# Parallel_CS_Prototype_multiple_sources.net
KiCad netlist of a schematic drawn in EAGLE
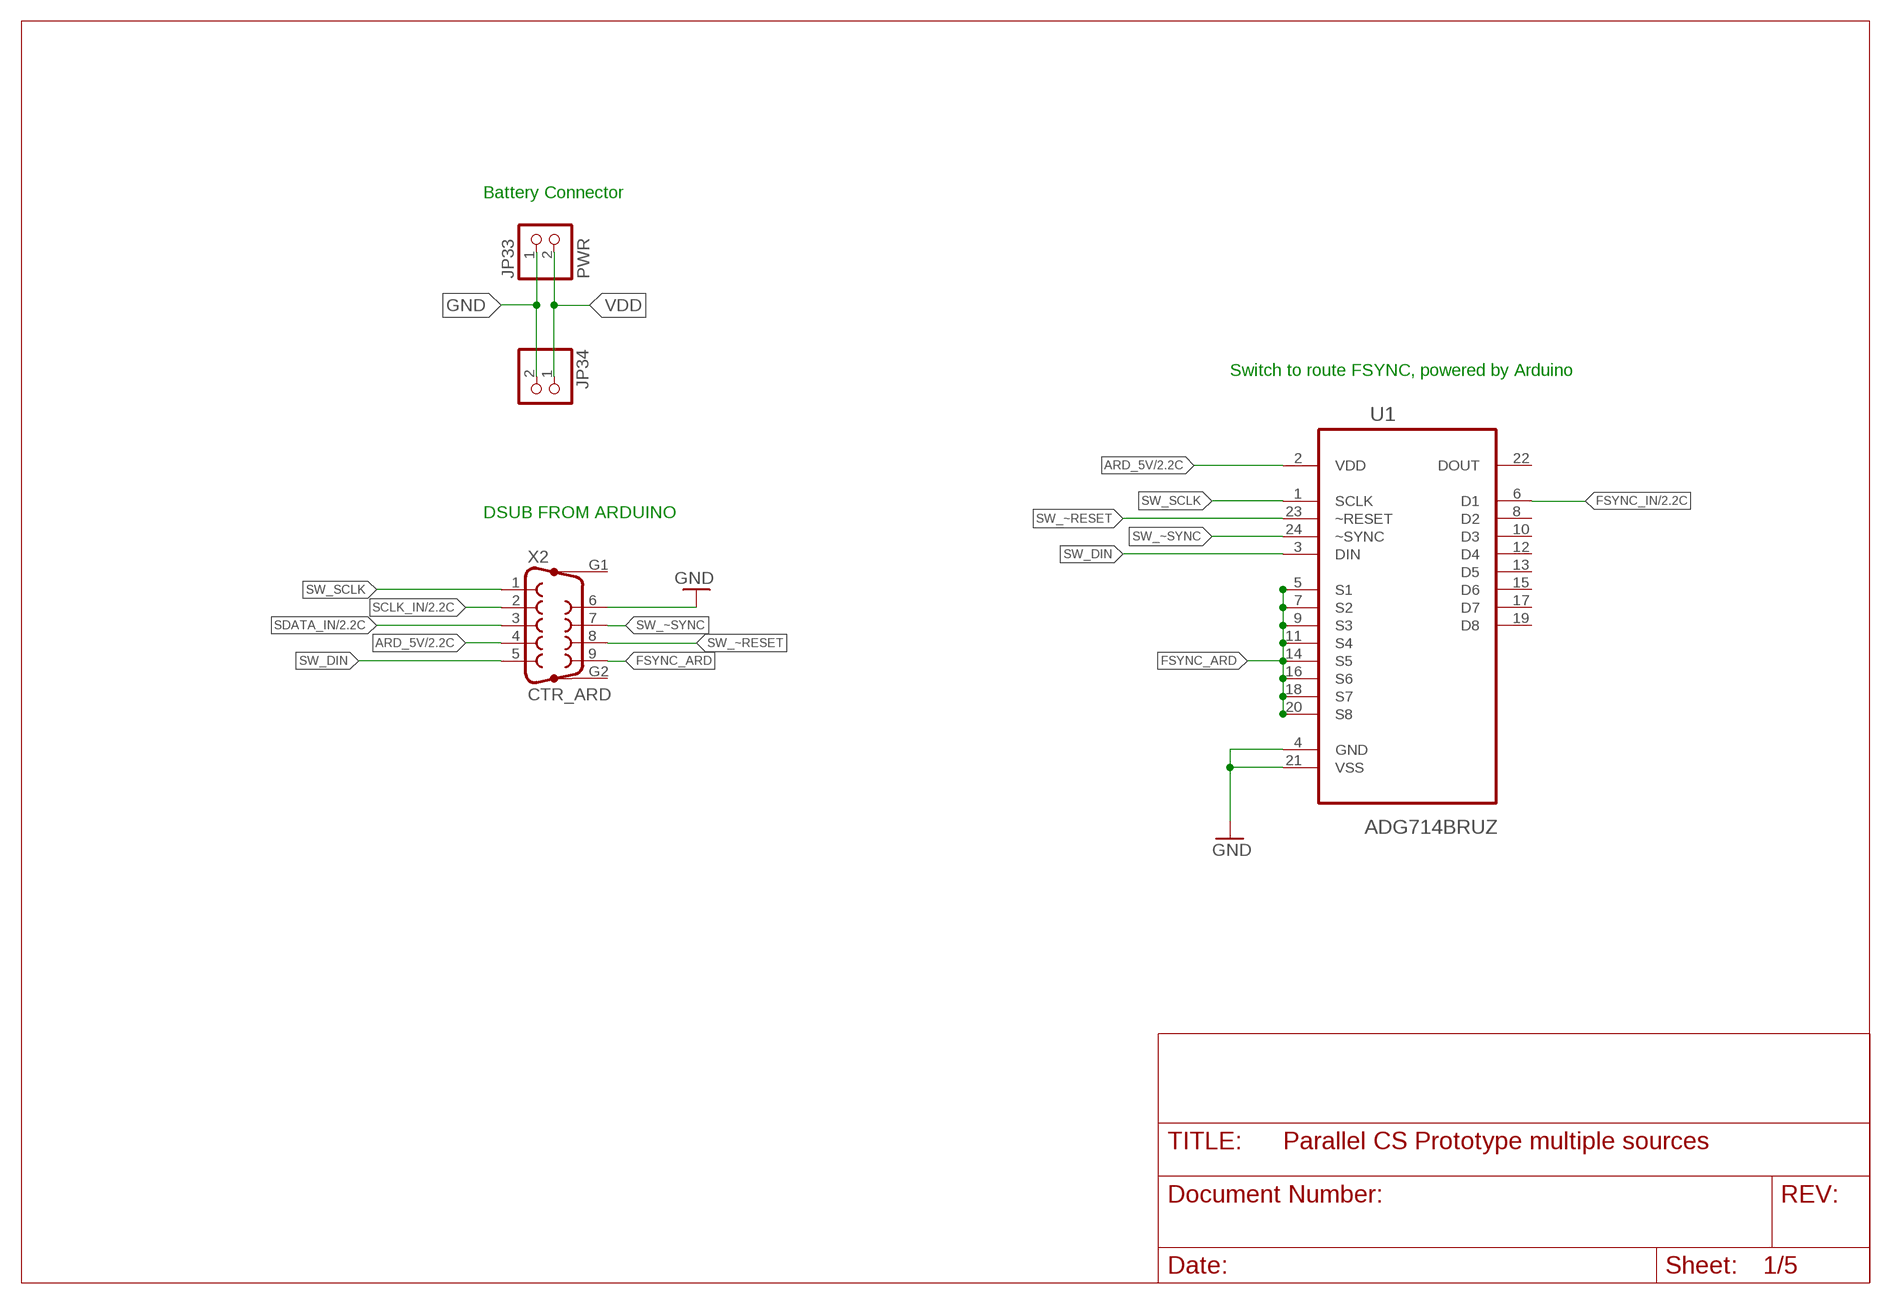
[diagram p0: schematic, sheet 1]
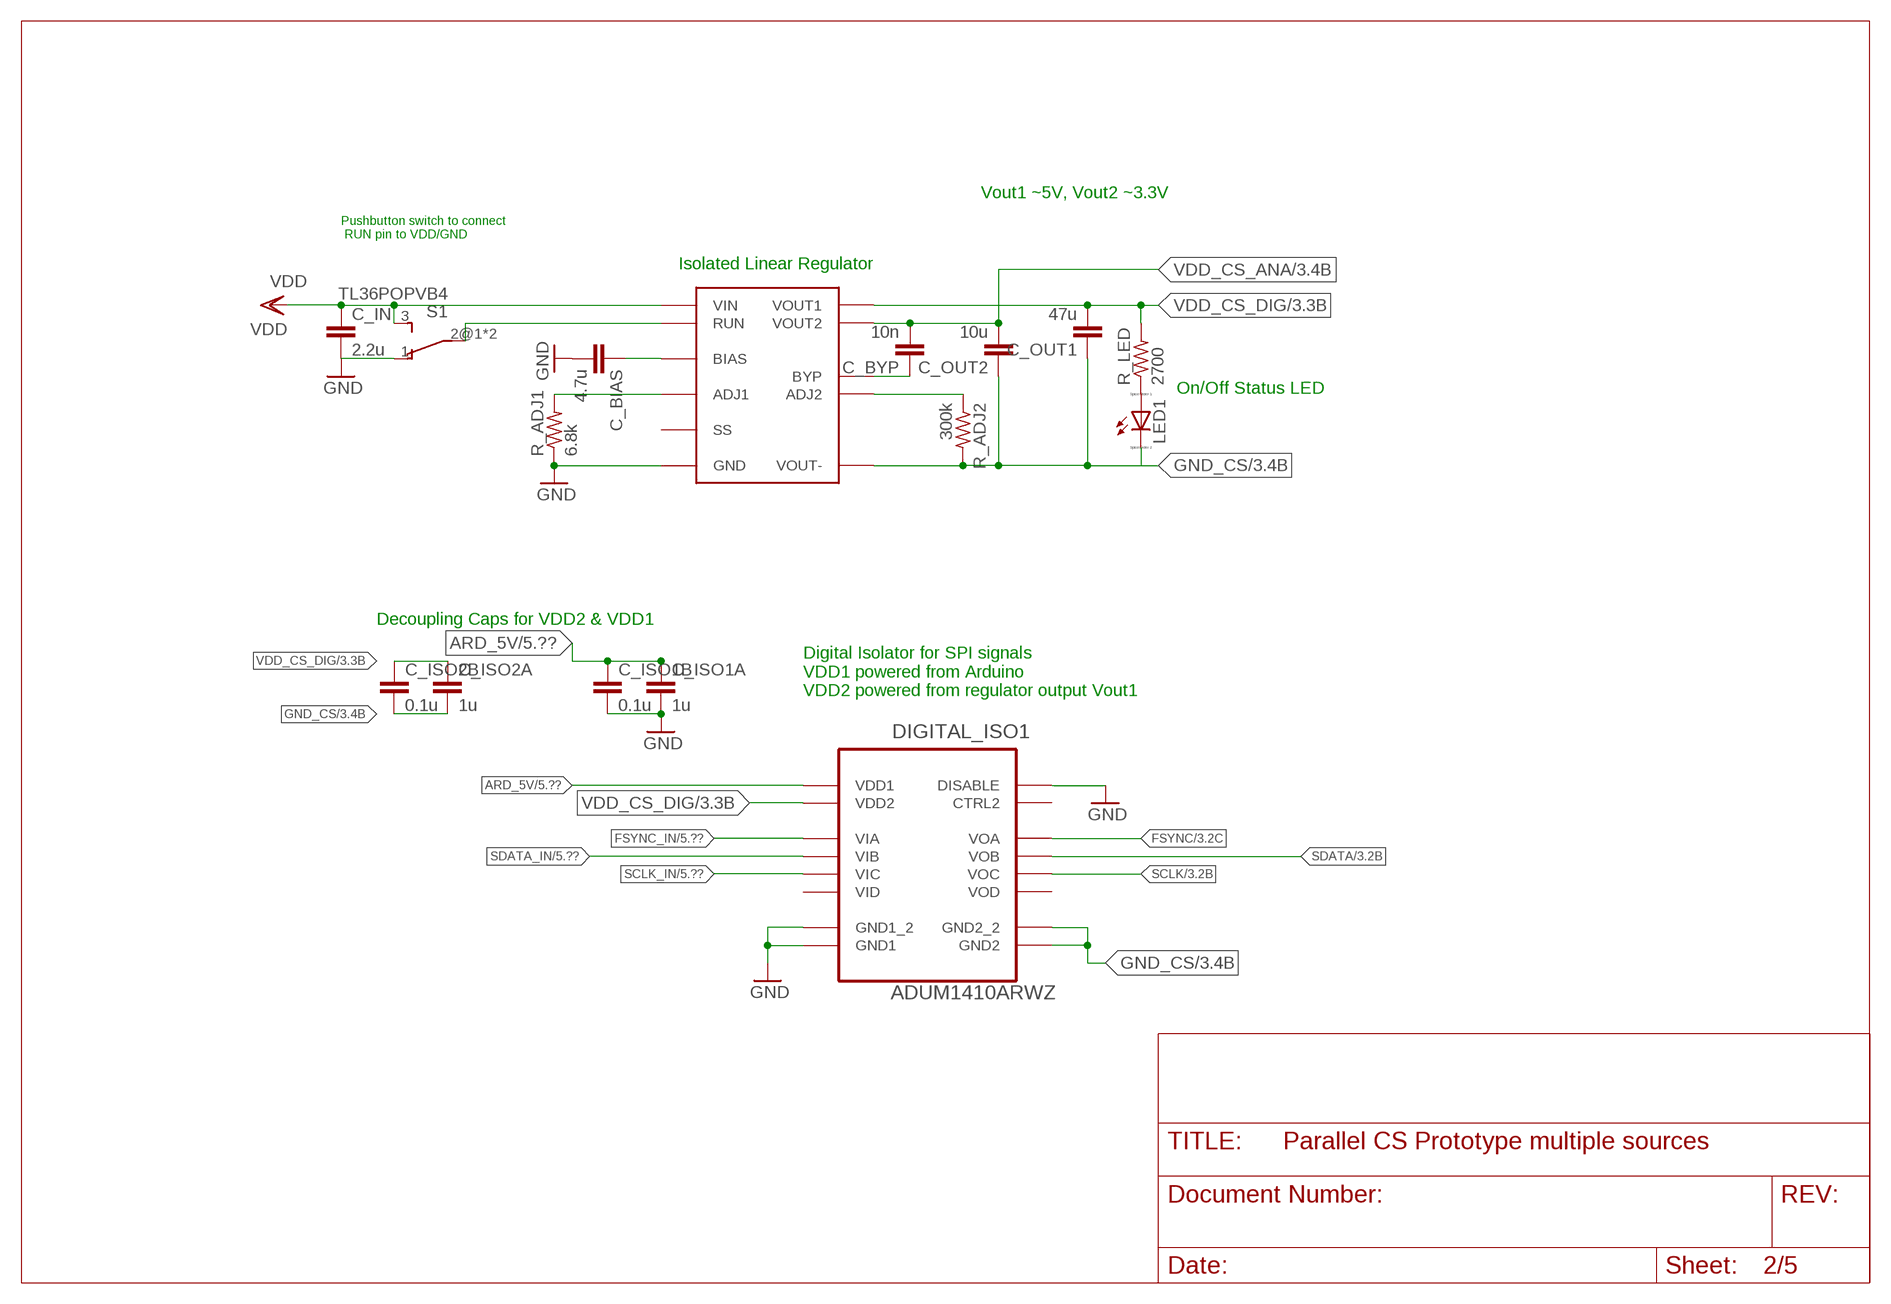
[diagram p1: schematic, sheet 2]
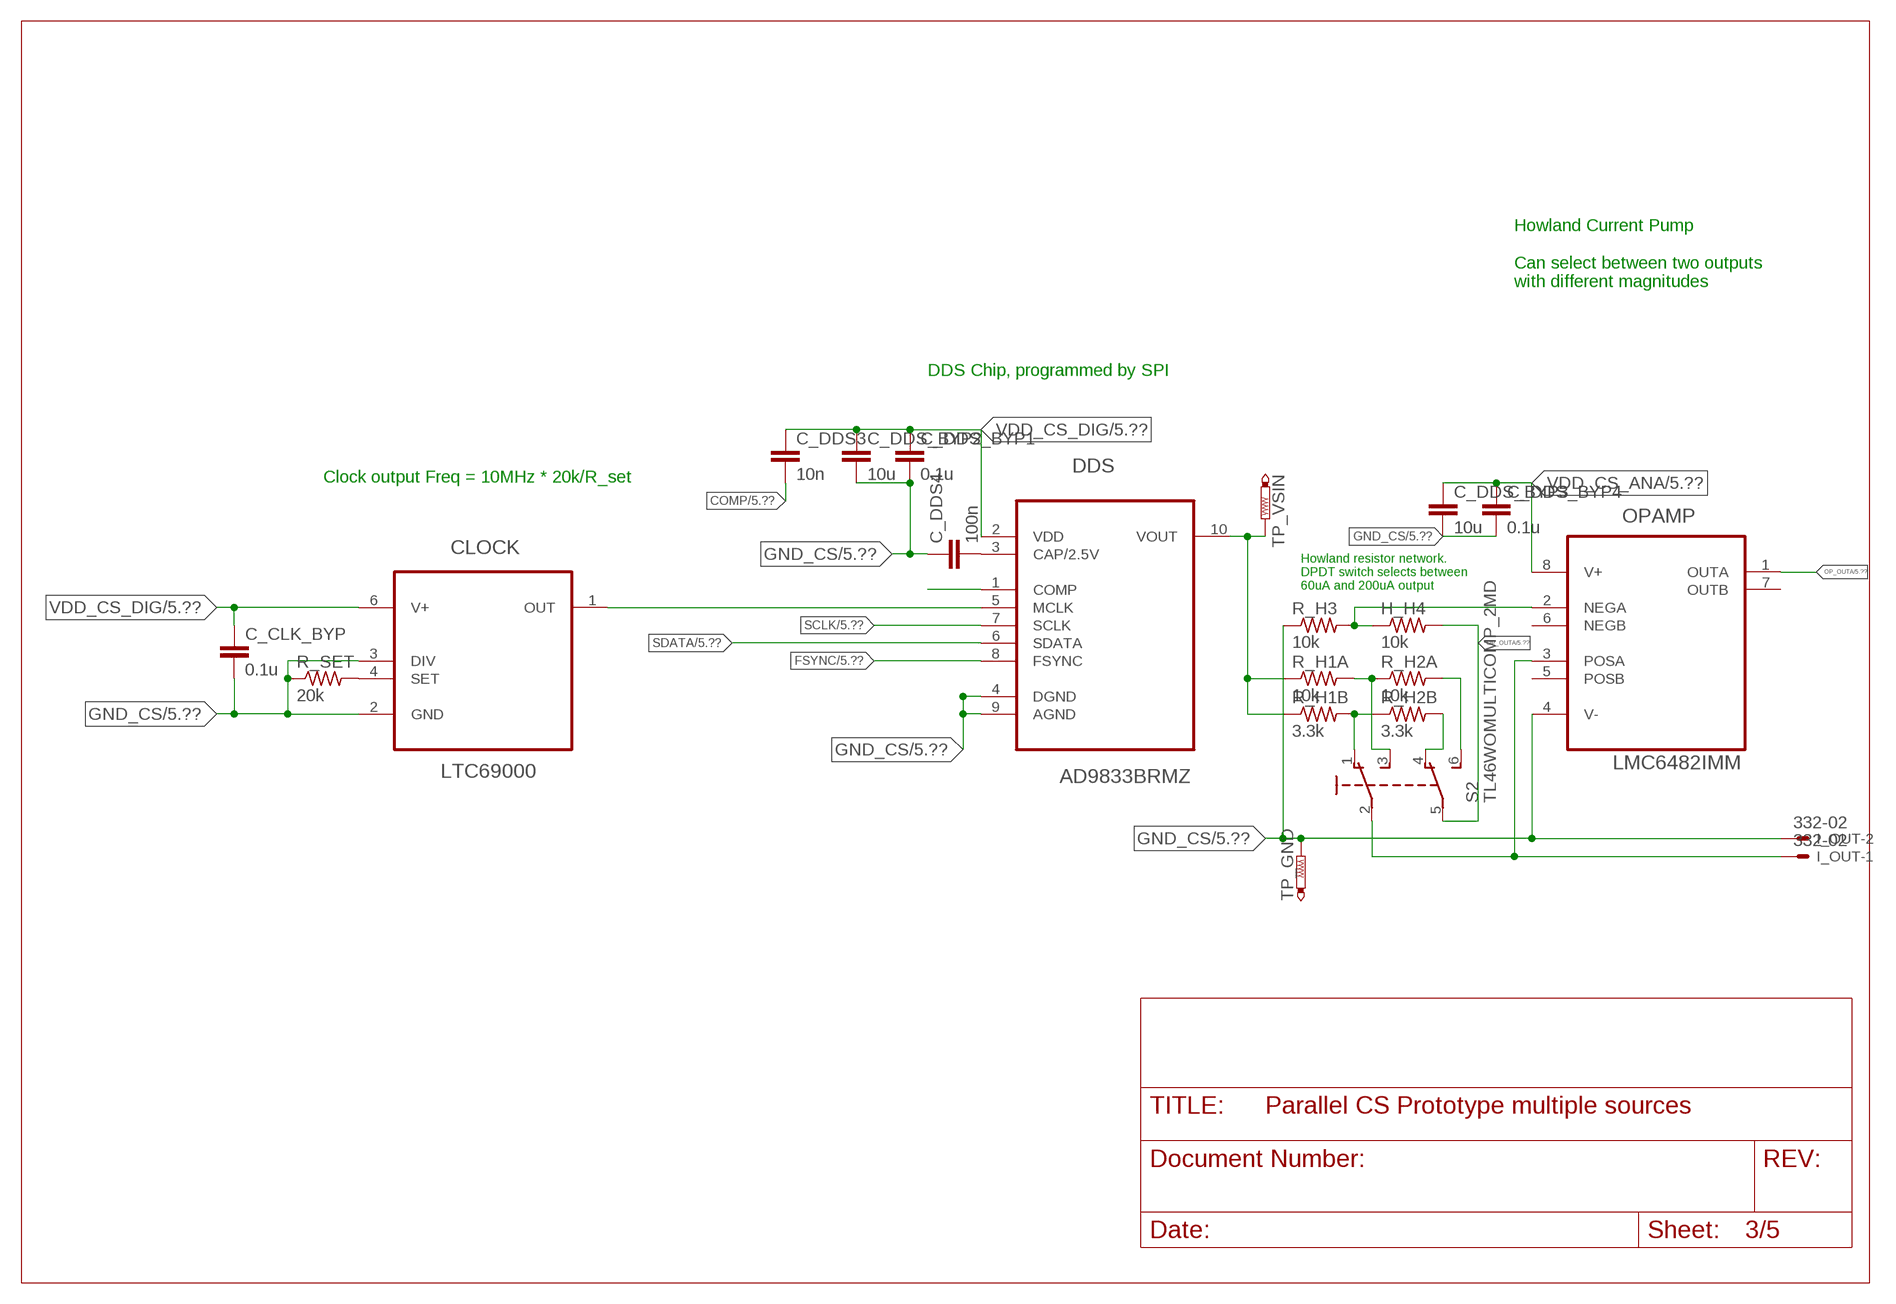
[diagram p2: schematic, sheet 3]
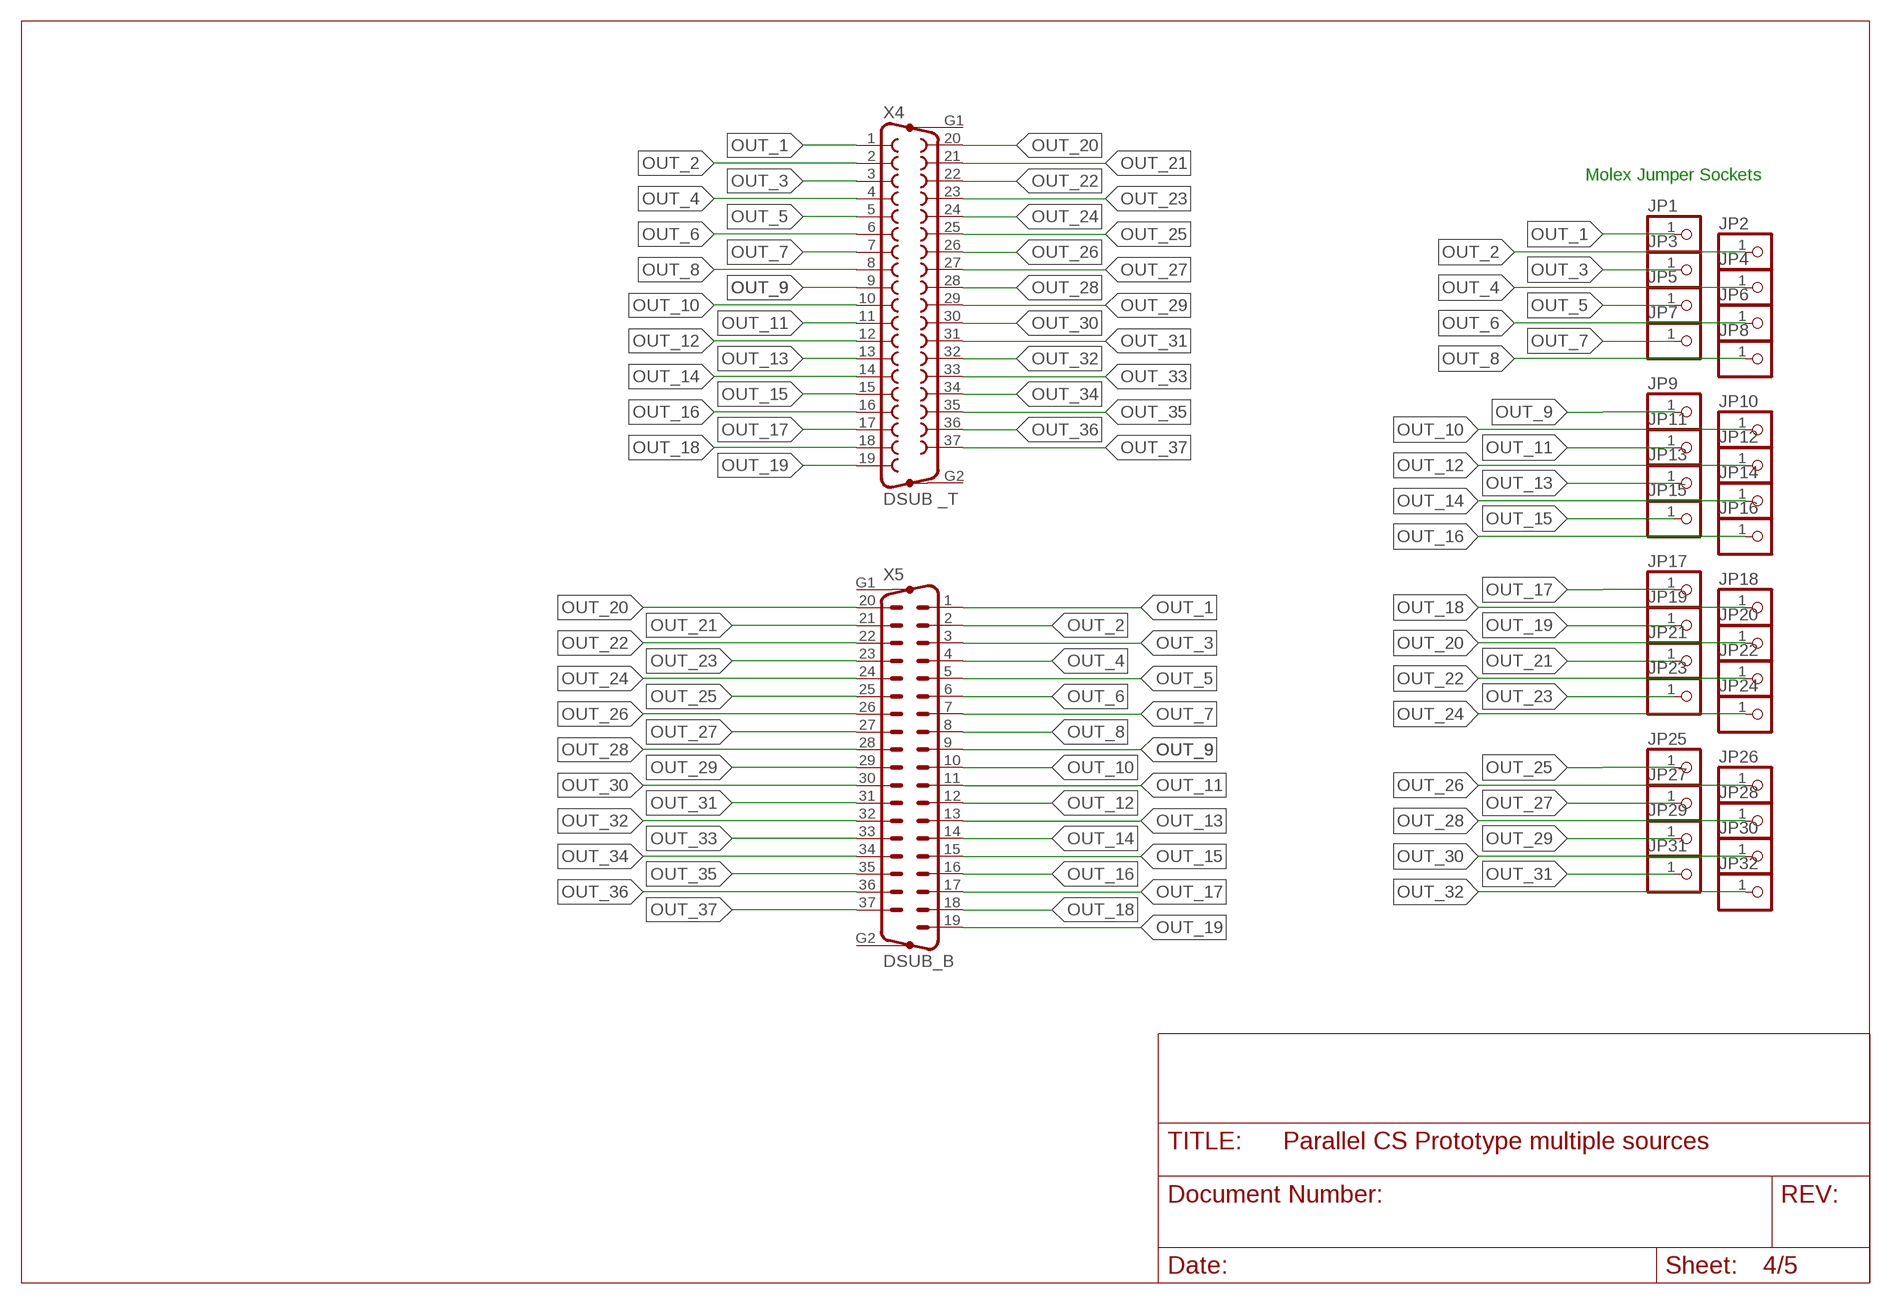
[diagram p3: schematic, sheet 4]
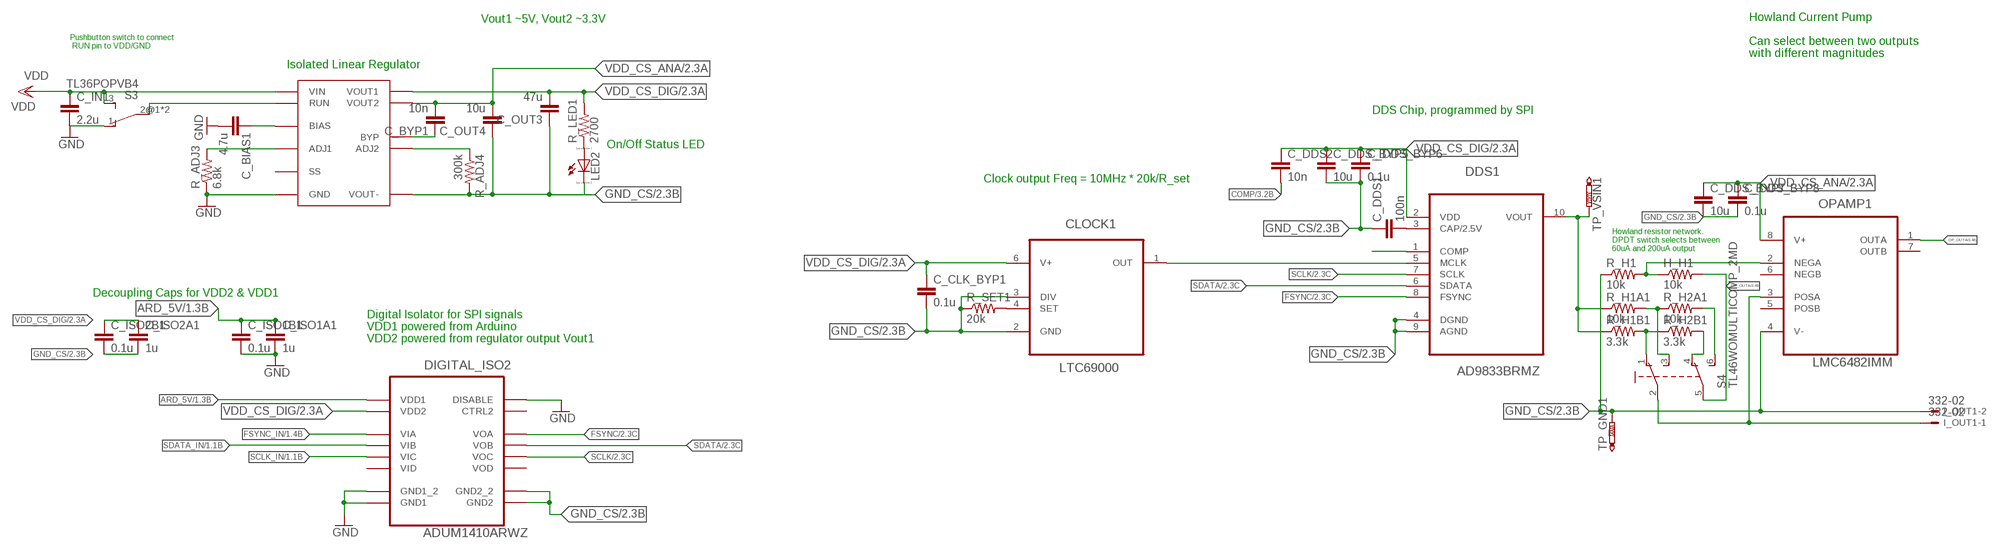
[diagram p4: schematic, sheet 5]

(export (version "E")
  (design (tool "Eeschema 10.0.6"))
  (components
    (comp (ref "CLOCK")
      (value "LTC69000")
      (footprint "eagle-import:SOT95P280X100-6N")
      (fields (field (name "MPN") "LTC6906IS6#PBF"))
      (libsource (lib "eagle-import") (part "LTC69000"))
    )
    (comp (ref "C_CLK_BYP")
      (value "0.1u")
      (footprint "eagle-import:C0402")
      (libsource (lib "eagle-import") (part "C-EUC0402"))
    )
    (comp (ref "C_DDS3")
      (value "10n")
      (footprint "eagle-import:C0402")
      (libsource (lib "eagle-import") (part "C-EUC0402"))
    )
    (comp (ref "C_DDS4")
      (value "100n")
      (footprint "eagle-import:C0402")
      (libsource (lib "eagle-import") (part "C-EUC0402"))
    )
    (comp (ref "C_DDS_BYP1")
      (value "0.1u")
      (footprint "eagle-import:C0402")
      (libsource (lib "eagle-import") (part "C-EUC0402"))
    )
    (comp (ref "C_DDS_BYP2")
      (value "10u")
      (footprint "eagle-import:C0402")
      (libsource (lib "eagle-import") (part "C-EUC0402"))
    )
    (comp (ref "C_DDS_BYP3")
      (value "10u")
      (footprint "eagle-import:C0402")
      (libsource (lib "eagle-import") (part "C-EUC0402"))
    )
    (comp (ref "C_DDS_BYP4")
      (value "0.1u")
      (footprint "eagle-import:C0402")
      (libsource (lib "eagle-import") (part "C-EUC0402"))
    )
    (comp (ref "DDS")
      (value "AD9833BRMZ")
      (footprint "eagle-import:SOP50P490X110-10N")
      (libsource (lib "eagle-import") (part "AD9833BRMZ"))
    )
    (comp (ref "H_H4")
      (value "10k")
      (footprint "eagle-import:R0603")
      (libsource (lib "eagle-import") (part "R-US_R0603"))
    )
    (comp (ref "I_OUT")
      (value "332-02")
      (footprint "eagle-import:332-02")
      (libsource (lib "eagle-import") (part "332-02"))
    )
    (comp (ref "OPAMP")
      (value "LMC6482IMM")
      (footprint "eagle-import:SOP65P490X109-8N")
      (libsource (lib "eagle-import") (part "LMC6482IMM"))
    )
    (comp (ref "R_H1A")
      (value "10k")
      (footprint "eagle-import:R0603")
      (libsource (lib "eagle-import") (part "R-US_R0603"))
    )
    (comp (ref "R_H1B")
      (value "3.3k")
      (footprint "eagle-import:R0603")
      (libsource (lib "eagle-import") (part "R-US_R0603"))
    )
    (comp (ref "R_H2A")
      (value "10k")
      (footprint "eagle-import:R0603")
      (libsource (lib "eagle-import") (part "R-US_R0603"))
    )
    (comp (ref "R_H2B")
      (value "3.3k")
      (footprint "eagle-import:R0603")
      (libsource (lib "eagle-import") (part "R-US_R0603"))
    )
    (comp (ref "R_H3")
      (value "10k")
      (footprint "eagle-import:R0603")
      (libsource (lib "eagle-import") (part "R-US_R0603"))
    )
    (comp (ref "R_SET")
      (value "20k")
      (footprint "eagle-import:R0603")
      (libsource (lib "eagle-import") (part "R-US_R0603"))
    )
    (comp (ref "S2")
      (value "TL46WOMULTICOMP_2MD")
      (footprint "eagle-import:TL4XPO")
      (libsource (lib "eagle-import") (part "TL46WOMULTICOMP_2MD"))
    )
    (comp (ref "TP_GND")
      (value "PTR1PAD1-13")
      (footprint "eagle-import:P1-13")
      (libsource (lib "eagle-import") (part "PTR1PAD1-13"))
    )
    (comp (ref "TP_VSIN")
      (value "PTR1PAD1-13")
      (footprint "eagle-import:P1-13")
      (libsource (lib "eagle-import") (part "PTR1PAD1-13"))
    )
    (comp (ref "C_BIAS")
      (value "4.7u")
      (footprint "eagle-import:C0805")
      (libsource (lib "eagle-import") (part "C-EUC0805"))
    )
    (comp (ref "C_BYP")
      (value "10n")
      (footprint "eagle-import:C0402")
      (libsource (lib "eagle-import") (part "C-EUC0402"))
    )
    (comp (ref "C_IN")
      (value "2.2u")
      (footprint "eagle-import:C0805")
      (libsource (lib "eagle-import") (part "C-EUC0805"))
    )
    (comp (ref "C_ISO1A")
      (value "1u")
      (footprint "eagle-import:C0402")
      (libsource (lib "eagle-import") (part "C-EUC0402"))
    )
    (comp (ref "C_ISO1B")
      (value "0.1u")
      (footprint "eagle-import:C0402")
      (libsource (lib "eagle-import") (part "C-EUC0402"))
    )
    (comp (ref "C_ISO2A")
      (value "1u")
      (footprint "eagle-import:C0402")
      (libsource (lib "eagle-import") (part "C-EUC0402"))
    )
    (comp (ref "C_ISO2B")
      (value "0.1u")
      (footprint "eagle-import:C0402")
      (libsource (lib "eagle-import") (part "C-EUC0402"))
    )
    (comp (ref "C_OUT1")
      (value "47u")
      (footprint "eagle-import:C0805")
      (libsource (lib "eagle-import") (part "C-EUC0805"))
    )
    (comp (ref "C_OUT2")
      (value "10u")
      (footprint "eagle-import:C0805")
      (libsource (lib "eagle-import") (part "C-EUC0805"))
    )
    (comp (ref "DIGITAL_ISO1")
      (value "ADUM1410ARWZ")
      (footprint "eagle-import:SOIC127P1032X265-16N")
      (libsource (lib "eagle-import") (part "ADUM1410ARWZ"))
    )
    (comp (ref "LED1")
      (value "LED_ESML0603")
      (footprint "eagle-import:LED_SML0603")
      (libsource (lib "eagle-import") (part "LED_ESML0603"))
    )
    (comp (ref "R_ADJ1")
      (value "6.8k")
      (footprint "eagle-import:R0201")
      (libsource (lib "eagle-import") (part "R-US_R0201"))
    )
    (comp (ref "R_ADJ2")
      (value "300k")
      (footprint "eagle-import:R0201")
      (libsource (lib "eagle-import") (part "R-US_R0201"))
    )
    (comp (ref "R_LED")
      (value "2700")
      (footprint "eagle-import:R0402")
      (libsource (lib "eagle-import") (part "R-US_R0402"))
    )
    (comp (ref "S1")
      (value "TL36POPVB4")
      (footprint "eagle-import:PVB4-EE")
      (libsource (lib "eagle-import") (part "TL36POPVB4"))
    )
    (comp (ref "U$1")
      (value "LTM8048")
      (footprint "eagle-import:BGA-49")
      (libsource (lib "eagle-import") (part "LTM8048"))
    )
    (comp (ref "CLOCK1")
      (value "LTC69000")
      (footprint "eagle-import:SOT95P280X100-6N")
      (fields (field (name "MPN") "LTC6906IS6#PBF"))
      (libsource (lib "eagle-import") (part "LTC69000"))
    )
    (comp (ref "C_BIAS1")
      (value "4.7u")
      (footprint "eagle-import:C0805")
      (libsource (lib "eagle-import") (part "C-EUC0805"))
    )
    (comp (ref "C_BYP1")
      (value "10n")
      (footprint "eagle-import:C0402")
      (libsource (lib "eagle-import") (part "C-EUC0402"))
    )
    (comp (ref "C_CLK_BYP1")
      (value "0.1u")
      (footprint "eagle-import:C0402")
      (libsource (lib "eagle-import") (part "C-EUC0402"))
    )
    (comp (ref "C_DDS1")
      (value "100n")
      (footprint "eagle-import:C0402")
      (libsource (lib "eagle-import") (part "C-EUC0402"))
    )
    (comp (ref "C_DDS2")
      (value "10n")
      (footprint "eagle-import:C0402")
      (libsource (lib "eagle-import") (part "C-EUC0402"))
    )
    (comp (ref "C_DDS_BYP5")
      (value "10u")
      (footprint "eagle-import:C0402")
      (libsource (lib "eagle-import") (part "C-EUC0402"))
    )
    (comp (ref "C_DDS_BYP6")
      (value "0.1u")
      (footprint "eagle-import:C0402")
      (libsource (lib "eagle-import") (part "C-EUC0402"))
    )
    (comp (ref "C_DDS_BYP7")
      (value "10u")
      (footprint "eagle-import:C0402")
      (libsource (lib "eagle-import") (part "C-EUC0402"))
    )
    (comp (ref "C_DDS_BYP8")
      (value "0.1u")
      (footprint "eagle-import:C0402")
      (libsource (lib "eagle-import") (part "C-EUC0402"))
    )
    (comp (ref "C_IN1")
      (value "2.2u")
      (footprint "eagle-import:C0805")
      (libsource (lib "eagle-import") (part "C-EUC0805"))
    )
    (comp (ref "C_ISO1A1")
      (value "1u")
      (footprint "eagle-import:C0402")
      (libsource (lib "eagle-import") (part "C-EUC0402"))
    )
    (comp (ref "C_ISO1B1")
      (value "0.1u")
      (footprint "eagle-import:C0402")
      (libsource (lib "eagle-import") (part "C-EUC0402"))
    )
    (comp (ref "C_ISO2A1")
      (value "1u")
      (footprint "eagle-import:C0402")
      (libsource (lib "eagle-import") (part "C-EUC0402"))
    )
    (comp (ref "C_ISO2B1")
      (value "0.1u")
      (footprint "eagle-import:C0402")
      (libsource (lib "eagle-import") (part "C-EUC0402"))
    )
    (comp (ref "C_OUT3")
      (value "47u")
      (footprint "eagle-import:C0805")
      (libsource (lib "eagle-import") (part "C-EUC0805"))
    )
    (comp (ref "C_OUT4")
      (value "10u")
      (footprint "eagle-import:C0805")
      (libsource (lib "eagle-import") (part "C-EUC0805"))
    )
    (comp (ref "DDS1")
      (value "AD9833BRMZ")
      (footprint "eagle-import:SOP50P490X110-10N")
      (libsource (lib "eagle-import") (part "AD9833BRMZ"))
    )
    (comp (ref "DIGITAL_ISO2")
      (value "ADUM1410ARWZ")
      (footprint "eagle-import:SOIC127P1032X265-16N")
      (libsource (lib "eagle-import") (part "ADUM1410ARWZ"))
    )
    (comp (ref "H_H1")
      (value "10k")
      (footprint "eagle-import:R0603")
      (libsource (lib "eagle-import") (part "R-US_R0603"))
    )
    (comp (ref "I_OUT1")
      (value "332-02")
      (footprint "eagle-import:332-02")
      (libsource (lib "eagle-import") (part "332-02"))
    )
    (comp (ref "LED2")
      (value "LED_ESML0603")
      (footprint "eagle-import:LED_SML0603")
      (libsource (lib "eagle-import") (part "LED_ESML0603"))
    )
    (comp (ref "OPAMP1")
      (value "LMC6482IMM")
      (footprint "eagle-import:SOP65P490X109-8N")
      (libsource (lib "eagle-import") (part "LMC6482IMM"))
    )
    (comp (ref "R_ADJ3")
      (value "6.8k")
      (footprint "eagle-import:R0201")
      (libsource (lib "eagle-import") (part "R-US_R0201"))
    )
    (comp (ref "R_ADJ4")
      (value "300k")
      (footprint "eagle-import:R0201")
      (libsource (lib "eagle-import") (part "R-US_R0201"))
    )
    (comp (ref "R_H1")
      (value "10k")
      (footprint "eagle-import:R0603")
      (libsource (lib "eagle-import") (part "R-US_R0603"))
    )
    (comp (ref "R_H1A1")
      (value "10k")
      (footprint "eagle-import:R0603")
      (libsource (lib "eagle-import") (part "R-US_R0603"))
    )
    (comp (ref "R_H1B1")
      (value "3.3k")
      (footprint "eagle-import:R0603")
      (libsource (lib "eagle-import") (part "R-US_R0603"))
    )
    (comp (ref "R_H2A1")
      (value "10k")
      (footprint "eagle-import:R0603")
      (libsource (lib "eagle-import") (part "R-US_R0603"))
    )
    (comp (ref "R_H2B1")
      (value "3.3k")
      (footprint "eagle-import:R0603")
      (libsource (lib "eagle-import") (part "R-US_R0603"))
    )
    (comp (ref "R_LED1")
      (value "2700")
      (footprint "eagle-import:R0402")
      (libsource (lib "eagle-import") (part "R-US_R0402"))
    )
    (comp (ref "R_SET1")
      (value "20k")
      (footprint "eagle-import:R0603")
      (libsource (lib "eagle-import") (part "R-US_R0603"))
    )
    (comp (ref "S3")
      (value "TL36POPVB4")
      (footprint "eagle-import:PVB4-EE")
      (libsource (lib "eagle-import") (part "TL36POPVB4"))
    )
    (comp (ref "S4")
      (value "TL46WOMULTICOMP_2MD")
      (footprint "eagle-import:TL4XPO")
      (libsource (lib "eagle-import") (part "TL46WOMULTICOMP_2MD"))
    )
    (comp (ref "TP_GND1")
      (value "PTR1PAD1-13")
      (footprint "eagle-import:P1-13")
      (libsource (lib "eagle-import") (part "PTR1PAD1-13"))
    )
    (comp (ref "TP_VSIN1")
      (value "PTR1PAD1-13")
      (footprint "eagle-import:P1-13")
      (libsource (lib "eagle-import") (part "PTR1PAD1-13"))
    )
    (comp (ref "U$2")
      (value "LTM8048")
      (footprint "eagle-import:BGA-49")
      (libsource (lib "eagle-import") (part "LTM8048"))
    )
    (comp (ref "JP1")
      (value "PINHD-1X1")
      (footprint "eagle-import:1X01")
      (libsource (lib "eagle-import") (part "PINHD-1X1"))
    )
    (comp (ref "JP2")
      (value "PINHD-1X1")
      (footprint "eagle-import:1X01")
      (libsource (lib "eagle-import") (part "PINHD-1X1"))
    )
    (comp (ref "JP3")
      (value "PINHD-1X1")
      (footprint "eagle-import:1X01")
      (libsource (lib "eagle-import") (part "PINHD-1X1"))
    )
    (comp (ref "JP4")
      (value "PINHD-1X1")
      (footprint "eagle-import:1X01")
      (libsource (lib "eagle-import") (part "PINHD-1X1"))
    )
    (comp (ref "JP5")
      (value "PINHD-1X1")
      (footprint "eagle-import:1X01")
      (libsource (lib "eagle-import") (part "PINHD-1X1"))
    )
    (comp (ref "JP6")
      (value "PINHD-1X1")
      (footprint "eagle-import:1X01")
      (libsource (lib "eagle-import") (part "PINHD-1X1"))
    )
    (comp (ref "JP7")
      (value "PINHD-1X1")
      (footprint "eagle-import:1X01")
      (libsource (lib "eagle-import") (part "PINHD-1X1"))
    )
    (comp (ref "JP8")
      (value "PINHD-1X1")
      (footprint "eagle-import:1X01")
      (libsource (lib "eagle-import") (part "PINHD-1X1"))
    )
    (comp (ref "JP9")
      (value "PINHD-1X1")
      (footprint "eagle-import:1X01")
      (libsource (lib "eagle-import") (part "PINHD-1X1"))
    )
    (comp (ref "JP10")
      (value "PINHD-1X1")
      (footprint "eagle-import:1X01")
      (libsource (lib "eagle-import") (part "PINHD-1X1"))
    )
    (comp (ref "JP11")
      (value "PINHD-1X1")
      (footprint "eagle-import:1X01")
      (libsource (lib "eagle-import") (part "PINHD-1X1"))
    )
    (comp (ref "JP12")
      (value "PINHD-1X1")
      (footprint "eagle-import:1X01")
      (libsource (lib "eagle-import") (part "PINHD-1X1"))
    )
    (comp (ref "JP13")
      (value "PINHD-1X1")
      (footprint "eagle-import:1X01")
      (libsource (lib "eagle-import") (part "PINHD-1X1"))
    )
    (comp (ref "JP14")
      (value "PINHD-1X1")
      (footprint "eagle-import:1X01")
      (libsource (lib "eagle-import") (part "PINHD-1X1"))
    )
    (comp (ref "JP15")
      (value "PINHD-1X1")
      (footprint "eagle-import:1X01")
      (libsource (lib "eagle-import") (part "PINHD-1X1"))
    )
    (comp (ref "JP16")
      (value "PINHD-1X1")
      (footprint "eagle-import:1X01")
      (libsource (lib "eagle-import") (part "PINHD-1X1"))
    )
    (comp (ref "JP17")
      (value "PINHD-1X1")
      (footprint "eagle-import:1X01")
      (libsource (lib "eagle-import") (part "PINHD-1X1"))
    )
    (comp (ref "JP18")
      (value "PINHD-1X1")
      (footprint "eagle-import:1X01")
      (libsource (lib "eagle-import") (part "PINHD-1X1"))
    )
    (comp (ref "JP19")
      (value "PINHD-1X1")
      (footprint "eagle-import:1X01")
      (libsource (lib "eagle-import") (part "PINHD-1X1"))
    )
    (comp (ref "JP20")
      (value "PINHD-1X1")
      (footprint "eagle-import:1X01")
      (libsource (lib "eagle-import") (part "PINHD-1X1"))
    )
    (comp (ref "JP21")
      (value "PINHD-1X1")
      (footprint "eagle-import:1X01")
      (libsource (lib "eagle-import") (part "PINHD-1X1"))
    )
    (comp (ref "JP22")
      (value "PINHD-1X1")
      (footprint "eagle-import:1X01")
      (libsource (lib "eagle-import") (part "PINHD-1X1"))
    )
    (comp (ref "JP23")
      (value "PINHD-1X1")
      (footprint "eagle-import:1X01")
      (libsource (lib "eagle-import") (part "PINHD-1X1"))
    )
    (comp (ref "JP24")
      (value "PINHD-1X1")
      (footprint "eagle-import:1X01")
      (libsource (lib "eagle-import") (part "PINHD-1X1"))
    )
    (comp (ref "JP25")
      (value "PINHD-1X1")
      (footprint "eagle-import:1X01")
      (libsource (lib "eagle-import") (part "PINHD-1X1"))
    )
    (comp (ref "JP26")
      (value "PINHD-1X1")
      (footprint "eagle-import:1X01")
      (libsource (lib "eagle-import") (part "PINHD-1X1"))
    )
    (comp (ref "JP27")
      (value "PINHD-1X1")
      (footprint "eagle-import:1X01")
      (libsource (lib "eagle-import") (part "PINHD-1X1"))
    )
    (comp (ref "JP28")
      (value "PINHD-1X1")
      (footprint "eagle-import:1X01")
      (libsource (lib "eagle-import") (part "PINHD-1X1"))
    )
    (comp (ref "JP29")
      (value "PINHD-1X1")
      (footprint "eagle-import:1X01")
      (libsource (lib "eagle-import") (part "PINHD-1X1"))
    )
    (comp (ref "JP30")
      (value "PINHD-1X1")
      (footprint "eagle-import:1X01")
      (libsource (lib "eagle-import") (part "PINHD-1X1"))
    )
    (comp (ref "JP31")
      (value "PINHD-1X1")
      (footprint "eagle-import:1X01")
      (libsource (lib "eagle-import") (part "PINHD-1X1"))
    )
    (comp (ref "JP32")
      (value "PINHD-1X1")
      (footprint "eagle-import:1X01")
      (libsource (lib "eagle-import") (part "PINHD-1X1"))
    )
    (comp (ref "X4")
      (value "DSUB _T")
      (footprint "eagle-import:F37HP")
      (libsource (lib "eagle-import") (part "F37HP"))
    )
    (comp (ref "X5")
      (value "DSUB_B")
      (footprint "eagle-import:M37HP")
      (libsource (lib "eagle-import") (part "M37HP"))
    )
    (comp (ref "JP33")
      (value "PWR")
      (footprint "eagle-import:1X02")
      (libsource (lib "eagle-import") (part "pinhead_PINHD-1X2"))
    )
    (comp (ref "JP34")
      (value "PINHD-1X2")
      (footprint "eagle-import:1X02")
      (libsource (lib "eagle-import") (part "PINHD-1X2"))
    )
    (comp (ref "U1")
      (value "ADG714BRUZ")
      (footprint "eagle-import:SOP65P640X120-24N")
      (libsource (lib "eagle-import") (part "ADG714BRUZ"))
    )
    (comp (ref "X2")
      (value "CTR_ARD")
      (footprint "eagle-import:F09HP")
      (libsource (lib "eagle-import") (part "F09HP"))
    )
  )
  (nets
    (net (code "1") (name "ARD_5V") (class "Default")
      (node (ref "C_ISO1A") (pin "1") (pinfunction "1_1") (pintype "passive"))
      (node (ref "C_ISO1A1") (pin "1") (pinfunction "1_1") (pintype "passive"))
      (node (ref "C_ISO1B") (pin "1") (pinfunction "1_1") (pintype "passive"))
      (node (ref "C_ISO1B1") (pin "1") (pinfunction "1_1") (pintype "passive"))
      (node (ref "DIGITAL_ISO1") (pin "1") (pinfunction "VDD1_1") (pintype "power_in"))
      (node (ref "DIGITAL_ISO2") (pin "1") (pinfunction "VDD1_1") (pintype "power_in"))
      (node (ref "U1") (pin "2") (pinfunction "VDD_2") (pintype "power_in"))
      (node (ref "X2") (pin "4") (pinfunction "4_4") (pintype "passive"))
    )
    (net (code "2") (name "COMP") (class "Default")
      (node (ref "C_DDS2") (pin "2") (pinfunction "2_2") (pintype "passive"))
      (node (ref "C_DDS3") (pin "2") (pinfunction "2_2") (pintype "passive"))
      (node (ref "DDS") (pin "1") (pinfunction "COMP_1") (pintype "passive"))
      (node (ref "DDS1") (pin "1") (pinfunction "COMP_1") (pintype "passive"))
    )
    (net (code "3") (name "FSYNC") (class "Default")
      (node (ref "DDS") (pin "8") (pinfunction "FSYNC_8") (pintype "input"))
      (node (ref "DDS1") (pin "8") (pinfunction "FSYNC_8") (pintype "input"))
      (node (ref "DIGITAL_ISO1") (pin "14") (pinfunction "VOA_14") (pintype "passive"))
      (node (ref "DIGITAL_ISO2") (pin "14") (pinfunction "VOA_14") (pintype "passive"))
    )
    (net (code "4") (name "FSYNC_ARD") (class "Default")
      (node (ref "U1") (pin "11") (pinfunction "S4_11") (pintype "bidirectional"))
      (node (ref "U1") (pin "14") (pinfunction "S5_14") (pintype "bidirectional"))
      (node (ref "U1") (pin "16") (pinfunction "S6_16") (pintype "bidirectional"))
      (node (ref "U1") (pin "18") (pinfunction "S7_18") (pintype "bidirectional"))
      (node (ref "U1") (pin "20") (pinfunction "S8_20") (pintype "bidirectional"))
      (node (ref "U1") (pin "5") (pinfunction "S1_5") (pintype "bidirectional"))
      (node (ref "U1") (pin "7") (pinfunction "S2_7") (pintype "bidirectional"))
      (node (ref "U1") (pin "9") (pinfunction "S3_9") (pintype "bidirectional"))
      (node (ref "X2") (pin "9") (pinfunction "9_9") (pintype "passive"))
    )
    (net (code "5") (name "FSYNC_IN") (class "Default")
      (node (ref "DIGITAL_ISO1") (pin "3") (pinfunction "VIA_3") (pintype "passive"))
      (node (ref "DIGITAL_ISO2") (pin "3") (pinfunction "VIA_3") (pintype "passive"))
      (node (ref "U1") (pin "6") (pinfunction "D1_6") (pintype "bidirectional"))
    )
    (net (code "6") (name "GND") (class "Default")
      (node (ref "C_BIAS") (pin "2") (pinfunction "2_2") (pintype "passive"))
      (node (ref "C_BIAS1") (pin "2") (pinfunction "2_2") (pintype "passive"))
      (node (ref "C_IN") (pin "2") (pinfunction "2_2") (pintype "passive"))
      (node (ref "C_IN1") (pin "2") (pinfunction "2_2") (pintype "passive"))
      (node (ref "C_ISO1A") (pin "2") (pinfunction "2_2") (pintype "passive"))
      (node (ref "C_ISO1A1") (pin "2") (pinfunction "2_2") (pintype "passive"))
      (node (ref "C_ISO1B") (pin "2") (pinfunction "2_2") (pintype "passive"))
      (node (ref "C_ISO1B1") (pin "2") (pinfunction "2_2") (pintype "passive"))
      (node (ref "DIGITAL_ISO1") (pin "2") (pinfunction "GND1_2_2") (pintype "passive"))
      (node (ref "DIGITAL_ISO1") (pin "7") (pinfunction "DISABLE_7") (pintype "passive"))
      (node (ref "DIGITAL_ISO1") (pin "8") (pinfunction "GND1_8") (pintype "passive"))
      (node (ref "DIGITAL_ISO2") (pin "2") (pinfunction "GND1_2_2") (pintype "passive"))
      (node (ref "DIGITAL_ISO2") (pin "7") (pinfunction "DISABLE_7") (pintype "passive"))
      (node (ref "DIGITAL_ISO2") (pin "8") (pinfunction "GND1_8") (pintype "passive"))
      (node (ref "JP33") (pin "1") (pinfunction "1_1") (pintype "passive"))
      (node (ref "JP34") (pin "2") (pinfunction "2_2") (pintype "passive"))
      (node (ref "R_ADJ1") (pin "1") (pinfunction "1_1") (pintype "passive"))
      (node (ref "R_ADJ3") (pin "1") (pinfunction "1_1") (pintype "passive"))
      (node (ref "S1") (pin "1") (pinfunction "O_1") (pintype "passive"))
      (node (ref "S3") (pin "1") (pinfunction "O_1") (pintype "passive"))
      (node (ref "U$1") (pin "GND@1") (pinfunction "GND_GND@1") (pintype "bidirectional"))
      (node (ref "U$1") (pin "GND@10") (pinfunction "GND_GND@10") (pintype "bidirectional"))
      (node (ref "U$1") (pin "GND@11") (pinfunction "GND_GND@11") (pintype "bidirectional"))
      (node (ref "U$1") (pin "GND@12") (pinfunction "GND_GND@12") (pintype "bidirectional"))
      (node (ref "U$1") (pin "GND@13") (pinfunction "GND_GND@13") (pintype "bidirectional"))
      (node (ref "U$1") (pin "GND@14") (pinfunction "GND_GND@14") (pintype "bidirectional"))
      (node (ref "U$1") (pin "GND@15") (pinfunction "GND_GND@15") (pintype "bidirectional"))
      (node (ref "U$1") (pin "GND@16") (pinfunction "GND_GND@16") (pintype "bidirectional"))
      (node (ref "U$1") (pin "GND@2") (pinfunction "GND_GND@2") (pintype "bidirectional"))
      (node (ref "U$1") (pin "GND@3") (pinfunction "GND_GND@3") (pintype "bidirectional"))
      (node (ref "U$1") (pin "GND@4") (pinfunction "GND_GND@4") (pintype "bidirectional"))
      (node (ref "U$1") (pin "GND@5") (pinfunction "GND_GND@5") (pintype "bidirectional"))
      (node (ref "U$1") (pin "GND@6") (pinfunction "GND_GND@6") (pintype "bidirectional"))
      (node (ref "U$1") (pin "GND@7") (pinfunction "GND_GND@7") (pintype "bidirectional"))
      (node (ref "U$1") (pin "GND@8") (pinfunction "GND_GND@8") (pintype "bidirectional"))
      (node (ref "U$1") (pin "GND@9") (pinfunction "GND_GND@9") (pintype "bidirectional"))
      (node (ref "U$2") (pin "GND@1") (pinfunction "GND_GND@1") (pintype "bidirectional"))
      (node (ref "U$2") (pin "GND@10") (pinfunction "GND_GND@10") (pintype "bidirectional"))
      (node (ref "U$2") (pin "GND@11") (pinfunction "GND_GND@11") (pintype "bidirectional"))
      (node (ref "U$2") (pin "GND@12") (pinfunction "GND_GND@12") (pintype "bidirectional"))
      (node (ref "U$2") (pin "GND@13") (pinfunction "GND_GND@13") (pintype "bidirectional"))
      (node (ref "U$2") (pin "GND@14") (pinfunction "GND_GND@14") (pintype "bidirectional"))
      (node (ref "U$2") (pin "GND@15") (pinfunction "GND_GND@15") (pintype "bidirectional"))
      (node (ref "U$2") (pin "GND@16") (pinfunction "GND_GND@16") (pintype "bidirectional"))
      (node (ref "U$2") (pin "GND@2") (pinfunction "GND_GND@2") (pintype "bidirectional"))
      (node (ref "U$2") (pin "GND@3") (pinfunction "GND_GND@3") (pintype "bidirectional"))
      (node (ref "U$2") (pin "GND@4") (pinfunction "GND_GND@4") (pintype "bidirectional"))
      (node (ref "U$2") (pin "GND@5") (pinfunction "GND_GND@5") (pintype "bidirectional"))
      (node (ref "U$2") (pin "GND@6") (pinfunction "GND_GND@6") (pintype "bidirectional"))
      (node (ref "U$2") (pin "GND@7") (pinfunction "GND_GND@7") (pintype "bidirectional"))
      (node (ref "U$2") (pin "GND@8") (pinfunction "GND_GND@8") (pintype "bidirectional"))
      (node (ref "U$2") (pin "GND@9") (pinfunction "GND_GND@9") (pintype "bidirectional"))
      (node (ref "U1") (pin "21") (pinfunction "VSS_21") (pintype "power_in"))
      (node (ref "U1") (pin "4") (pinfunction "GND_4") (pintype "passive"))
      (node (ref "X2") (pin "6") (pinfunction "6_6") (pintype "passive"))
    )
    (net (code "7") (name "GND_CS") (class "Default")
      (node (ref "CLOCK") (pin "2") (pinfunction "GND_2") (pintype "passive"))
      (node (ref "CLOCK") (pin "3") (pinfunction "DIV_3") (pintype "input"))
      (node (ref "CLOCK1") (pin "2") (pinfunction "GND_2") (pintype "passive"))
      (node (ref "CLOCK1") (pin "3") (pinfunction "DIV_3") (pintype "input"))
      (node (ref "C_CLK_BYP") (pin "2") (pinfunction "2_2") (pintype "passive"))
      (node (ref "C_CLK_BYP1") (pin "2") (pinfunction "2_2") (pintype "passive"))
      (node (ref "C_DDS1") (pin "1") (pinfunction "1_1") (pintype "passive"))
      (node (ref "C_DDS4") (pin "1") (pinfunction "1_1") (pintype "passive"))
      (node (ref "C_DDS_BYP1") (pin "2") (pinfunction "2_2") (pintype "passive"))
      (node (ref "C_DDS_BYP2") (pin "2") (pinfunction "2_2") (pintype "passive"))
      (node (ref "C_DDS_BYP3") (pin "2") (pinfunction "2_2") (pintype "passive"))
      (node (ref "C_DDS_BYP4") (pin "2") (pinfunction "2_2") (pintype "passive"))
      (node (ref "C_DDS_BYP5") (pin "2") (pinfunction "2_2") (pintype "passive"))
      (node (ref "C_DDS_BYP6") (pin "2") (pinfunction "2_2") (pintype "passive"))
      (node (ref "C_DDS_BYP7") (pin "2") (pinfunction "2_2") (pintype "passive"))
      (node (ref "C_DDS_BYP8") (pin "2") (pinfunction "2_2") (pintype "passive"))
      (node (ref "C_ISO2A") (pin "2") (pinfunction "2_2") (pintype "passive"))
      (node (ref "C_ISO2A1") (pin "2") (pinfunction "2_2") (pintype "passive"))
      (node (ref "C_ISO2B") (pin "2") (pinfunction "2_2") (pintype "passive"))
      (node (ref "C_ISO2B1") (pin "2") (pinfunction "2_2") (pintype "passive"))
      (node (ref "C_OUT1") (pin "1") (pinfunction "1_1") (pintype "passive"))
      (node (ref "C_OUT2") (pin "1") (pinfunction "1_1") (pintype "passive"))
      (node (ref "C_OUT3") (pin "1") (pinfunction "1_1") (pintype "passive"))
      (node (ref "C_OUT4") (pin "1") (pinfunction "1_1") (pintype "passive"))
      (node (ref "DDS") (pin "4") (pinfunction "DGND_4") (pintype "passive"))
      (node (ref "DDS") (pin "9") (pinfunction "AGND_9") (pintype "passive"))
      (node (ref "DDS1") (pin "4") (pinfunction "DGND_4") (pintype "passive"))
      (node (ref "DDS1") (pin "9") (pinfunction "AGND_9") (pintype "passive"))
      (node (ref "DIGITAL_ISO1") (pin "15") (pinfunction "GND2_15") (pintype "passive"))
      (node (ref "DIGITAL_ISO1") (pin "9") (pinfunction "GND2_2_9") (pintype "passive"))
      (node (ref "DIGITAL_ISO2") (pin "15") (pinfunction "GND2_15") (pintype "passive"))
      (node (ref "DIGITAL_ISO2") (pin "9") (pinfunction "GND2_2_9") (pintype "passive"))
      (node (ref "I_OUT") (pin "2") (pinfunction "S_2") (pintype "passive"))
      (node (ref "I_OUT1") (pin "2") (pinfunction "S_2") (pintype "passive"))
      (node (ref "LED1") (pin "C") (pinfunction "C_C") (pintype "passive"))
      (node (ref "LED2") (pin "C") (pinfunction "C_C") (pintype "passive"))
      (node (ref "OPAMP") (pin "4") (pinfunction "V-_4") (pintype "power_in"))
      (node (ref "OPAMP1") (pin "4") (pinfunction "V-_4") (pintype "power_in"))
      (node (ref "R_ADJ2") (pin "2") (pinfunction "2_2") (pintype "passive"))
      (node (ref "R_ADJ4") (pin "2") (pinfunction "2_2") (pintype "passive"))
      (node (ref "R_H1") (pin "1") (pinfunction "1_1") (pintype "passive"))
      (node (ref "R_H3") (pin "1") (pinfunction "1_1") (pintype "passive"))
      (node (ref "R_SET") (pin "1") (pinfunction "1_1") (pintype "passive"))
      (node (ref "R_SET1") (pin "1") (pinfunction "1_1") (pintype "passive"))
      (node (ref "TP_GND") (pin "TP") (pinfunction "TP_TP") (pintype "input"))
      (node (ref "TP_GND1") (pin "TP") (pinfunction "TP_TP") (pintype "input"))
      (node (ref "U$1") (pin "VOUT-@1") (pinfunction "VOUT-_VOUT-@1") (pintype "bidirectional"))
      (node (ref "U$1") (pin "VOUT-@2") (pinfunction "VOUT-_VOUT-@2") (pintype "bidirectional"))
      (node (ref "U$1") (pin "VOUT-@3") (pinfunction "VOUT-_VOUT-@3") (pintype "bidirectional"))
      (node (ref "U$1") (pin "VOUT-@4") (pinfunction "VOUT-_VOUT-@4") (pintype "bidirectional"))
      (node (ref "U$1") (pin "VOUT-@5") (pinfunction "VOUT-_VOUT-@5") (pintype "bidirectional"))
      (node (ref "U$1") (pin "VOUT-@6") (pinfunction "VOUT-_VOUT-@6") (pintype "bidirectional"))
      (node (ref "U$1") (pin "VOUT-@7") (pinfunction "VOUT-_VOUT-@7") (pintype "bidirectional"))
      (node (ref "U$1") (pin "VOUT-@8") (pinfunction "VOUT-_VOUT-@8") (pintype "bidirectional"))
      (node (ref "U$1") (pin "VOUT-@9") (pinfunction "VOUT-_VOUT-@9") (pintype "bidirectional"))
      (node (ref "U$2") (pin "VOUT-@1") (pinfunction "VOUT-_VOUT-@1") (pintype "bidirectional"))
      (node (ref "U$2") (pin "VOUT-@2") (pinfunction "VOUT-_VOUT-@2") (pintype "bidirectional"))
      (node (ref "U$2") (pin "VOUT-@3") (pinfunction "VOUT-_VOUT-@3") (pintype "bidirectional"))
      (node (ref "U$2") (pin "VOUT-@4") (pinfunction "VOUT-_VOUT-@4") (pintype "bidirectional"))
      (node (ref "U$2") (pin "VOUT-@5") (pinfunction "VOUT-_VOUT-@5") (pintype "bidirectional"))
      (node (ref "U$2") (pin "VOUT-@6") (pinfunction "VOUT-_VOUT-@6") (pintype "bidirectional"))
      (node (ref "U$2") (pin "VOUT-@7") (pinfunction "VOUT-_VOUT-@7") (pintype "bidirectional"))
      (node (ref "U$2") (pin "VOUT-@8") (pinfunction "VOUT-_VOUT-@8") (pintype "bidirectional"))
      (node (ref "U$2") (pin "VOUT-@9") (pinfunction "VOUT-_VOUT-@9") (pintype "bidirectional"))
    )
    (net (code "8") (name "Net-(CLOCK-OUT)") (class "Default")
      (node (ref "CLOCK") (pin "1") (pinfunction "OUT_1") (pintype "output"))
      (node (ref "DDS") (pin "5") (pinfunction "MCLK_5") (pintype "input"))
    )
    (net (code "9") (name "Net-(CLOCK-SET)") (class "Default")
      (node (ref "CLOCK") (pin "4") (pinfunction "SET_4") (pintype "input"))
      (node (ref "R_SET") (pin "2") (pinfunction "2_2") (pintype "passive"))
    )
    (net (code "10") (name "Net-(CLOCK1-OUT)") (class "Default")
      (node (ref "CLOCK1") (pin "1") (pinfunction "OUT_1") (pintype "output"))
      (node (ref "DDS1") (pin "5") (pinfunction "MCLK_5") (pintype "input"))
    )
    (net (code "11") (name "Net-(CLOCK1-SET)") (class "Default")
      (node (ref "CLOCK1") (pin "4") (pinfunction "SET_4") (pintype "input"))
      (node (ref "R_SET1") (pin "2") (pinfunction "2_2") (pintype "passive"))
    )
    (net (code "12") (name "Net-(C_BIAS-Pad1)") (class "Default")
      (node (ref "C_BIAS") (pin "1") (pinfunction "1_1") (pintype "passive"))
      (node (ref "U$1") (pin "BIAS") (pinfunction "BIAS_BIAS") (pintype "bidirectional"))
    )
    (net (code "13") (name "Net-(C_BIAS1-Pad1)") (class "Default")
      (node (ref "C_BIAS1") (pin "1") (pinfunction "1_1") (pintype "passive"))
      (node (ref "U$2") (pin "BIAS") (pinfunction "BIAS_BIAS") (pintype "bidirectional"))
    )
    (net (code "14") (name "Net-(C_BYP-Pad1)") (class "Default")
      (node (ref "C_BYP") (pin "1") (pinfunction "1_1") (pintype "passive"))
      (node (ref "U$1") (pin "BYP") (pinfunction "BYP_BYP") (pintype "bidirectional"))
    )
    (net (code "15") (name "Net-(C_BYP1-Pad1)") (class "Default")
      (node (ref "C_BYP1") (pin "1") (pinfunction "1_1") (pintype "passive"))
      (node (ref "U$2") (pin "BYP") (pinfunction "BYP_BYP") (pintype "bidirectional"))
    )
    (net (code "16") (name "Net-(DDS-CAP{slash}2.5V)") (class "Default")
      (node (ref "C_DDS4") (pin "2") (pinfunction "2_2") (pintype "passive"))
      (node (ref "DDS") (pin "3") (pinfunction "CAP/2.5V_3") (pintype "passive"))
    )
    (net (code "17") (name "Net-(DDS-VOUT)") (class "Default")
      (node (ref "DDS") (pin "10") (pinfunction "VOUT_10") (pintype "output"))
      (node (ref "R_H1A") (pin "1") (pinfunction "1_1") (pintype "passive"))
      (node (ref "R_H1B") (pin "1") (pinfunction "1_1") (pintype "passive"))
      (node (ref "TP_VSIN") (pin "TP") (pinfunction "TP_TP") (pintype "input"))
    )
    (net (code "18") (name "Net-(DDS1-CAP{slash}2.5V)") (class "Default")
      (node (ref "C_DDS1") (pin "2") (pinfunction "2_2") (pintype "passive"))
      (node (ref "DDS1") (pin "3") (pinfunction "CAP/2.5V_3") (pintype "passive"))
    )
    (net (code "19") (name "Net-(DDS1-VOUT)") (class "Default")
      (node (ref "DDS1") (pin "10") (pinfunction "VOUT_10") (pintype "output"))
      (node (ref "R_H1A1") (pin "1") (pinfunction "1_1") (pintype "passive"))
      (node (ref "R_H1B1") (pin "1") (pinfunction "1_1") (pintype "passive"))
      (node (ref "TP_VSIN1") (pin "TP") (pinfunction "TP_TP") (pintype "input"))
    )
    (net (code "20") (name "Net-(I_OUT1A-S)") (class "Default")
      (node (ref "I_OUT1") (pin "1") (pinfunction "S_1") (pintype "passive"))
      (node (ref "OPAMP1") (pin "3") (pinfunction "POSA_3") (pintype "input"))
      (node (ref "S4") (pin "2") (pinfunction "P_2") (pintype "passive"))
    )
    (net (code "21") (name "Net-(I_OUTA-S)") (class "Default")
      (node (ref "I_OUT") (pin "1") (pinfunction "S_1") (pintype "passive"))
      (node (ref "OPAMP") (pin "3") (pinfunction "POSA_3") (pintype "input"))
      (node (ref "S2") (pin "2") (pinfunction "P_2") (pintype "passive"))
    )
    (net (code "22") (name "Net-(LED1-PadA)") (class "Default")
      (node (ref "LED1") (pin "A") (pinfunction "A_A") (pintype "passive"))
      (node (ref "R_LED") (pin "1") (pinfunction "1_1") (pintype "passive"))
    )
    (net (code "23") (name "Net-(LED2-PadA)") (class "Default")
      (node (ref "LED2") (pin "A") (pinfunction "A_A") (pintype "passive"))
      (node (ref "R_LED1") (pin "1") (pinfunction "1_1") (pintype "passive"))
    )
    (net (code "24") (name "Net-(OPAMP-NEGA)") (class "Default")
      (node (ref "H_H4") (pin "1") (pinfunction "1_1") (pintype "passive"))
      (node (ref "OPAMP") (pin "2") (pinfunction "NEGA_2") (pintype "input"))
      (node (ref "R_H3") (pin "2") (pinfunction "2_2") (pintype "passive"))
    )
    (net (code "25") (name "Net-(OPAMP1-NEGA)") (class "Default")
      (node (ref "H_H1") (pin "1") (pinfunction "1_1") (pintype "passive"))
      (node (ref "OPAMP1") (pin "2") (pinfunction "NEGA_2") (pintype "input"))
      (node (ref "R_H1") (pin "2") (pinfunction "2_2") (pintype "passive"))
    )
    (net (code "26") (name "Net-(R_ADJ1-Pad2)") (class "Default")
      (node (ref "R_ADJ1") (pin "2") (pinfunction "2_2") (pintype "passive"))
      (node (ref "U$1") (pin "ADJ1") (pinfunction "ADJ1_ADJ1") (pintype "bidirectional"))
    )
    (net (code "27") (name "Net-(R_ADJ2-Pad1)") (class "Default")
      (node (ref "R_ADJ2") (pin "1") (pinfunction "1_1") (pintype "passive"))
      (node (ref "U$1") (pin "ADJ2") (pinfunction "ADJ2_ADJ2") (pintype "bidirectional"))
    )
    (net (code "28") (name "Net-(R_ADJ3-Pad2)") (class "Default")
      (node (ref "R_ADJ3") (pin "2") (pinfunction "2_2") (pintype "passive"))
      (node (ref "U$2") (pin "ADJ1") (pinfunction "ADJ1_ADJ1") (pintype "bidirectional"))
    )
    (net (code "29") (name "Net-(R_ADJ4-Pad1)") (class "Default")
      (node (ref "R_ADJ4") (pin "1") (pinfunction "1_1") (pintype "passive"))
      (node (ref "U$2") (pin "ADJ2") (pinfunction "ADJ2_ADJ2") (pintype "bidirectional"))
    )
    (net (code "30") (name "Net-(S1-P-Pad2@1)") (class "Default")
      (node (ref "S1") (pin "2@1") (pinfunction "P_2@1") (pintype "passive"))
      (node (ref "S1") (pin "2@2") (pinfunction "P_2@2") (pintype "passive"))
      (node (ref "U$1") (pin "RUN") (pinfunction "RUN_RUN") (pintype "bidirectional"))
    )
    (net (code "31") (name "Net-(S2-O)") (class "Default")
      (node (ref "R_H1B") (pin "2") (pinfunction "2_2") (pintype "passive"))
      (node (ref "R_H2B") (pin "1") (pinfunction "1_1") (pintype "passive"))
      (node (ref "S2") (pin "1") (pinfunction "O_1") (pintype "passive"))
    )
    (net (code "32") (name "Net-(S2-O1)") (class "Default")
      (node (ref "R_H2B") (pin "2") (pinfunction "2_2") (pintype "passive"))
      (node (ref "S2") (pin "4") (pinfunction "O1_4") (pintype "passive"))
    )
    (net (code "33") (name "Net-(S2-S)") (class "Default")
      (node (ref "R_H1A") (pin "2") (pinfunction "2_2") (pintype "passive"))
      (node (ref "R_H2A") (pin "1") (pinfunction "1_1") (pintype "passive"))
      (node (ref "S2") (pin "3") (pinfunction "S_3") (pintype "passive"))
    )
    (net (code "34") (name "Net-(S2-S1)") (class "Default")
      (node (ref "R_H2A") (pin "2") (pinfunction "2_2") (pintype "passive"))
      (node (ref "S2") (pin "6") (pinfunction "S1_6") (pintype "passive"))
    )
    (net (code "35") (name "Net-(S3-P-Pad2@1)") (class "Default")
      (node (ref "S3") (pin "2@1") (pinfunction "P_2@1") (pintype "passive"))
      (node (ref "S3") (pin "2@2") (pinfunction "P_2@2") (pintype "passive"))
      (node (ref "U$2") (pin "RUN") (pinfunction "RUN_RUN") (pintype "bidirectional"))
    )
    (net (code "36") (name "Net-(S4-O)") (class "Default")
      (node (ref "R_H1B1") (pin "2") (pinfunction "2_2") (pintype "passive"))
      (node (ref "R_H2B1") (pin "1") (pinfunction "1_1") (pintype "passive"))
      (node (ref "S4") (pin "1") (pinfunction "O_1") (pintype "passive"))
    )
    (net (code "37") (name "Net-(S4-O1)") (class "Default")
      (node (ref "R_H2B1") (pin "2") (pinfunction "2_2") (pintype "passive"))
      (node (ref "S4") (pin "4") (pinfunction "O1_4") (pintype "passive"))
    )
    (net (code "38") (name "Net-(S4-S)") (class "Default")
      (node (ref "R_H1A1") (pin "2") (pinfunction "2_2") (pintype "passive"))
      (node (ref "R_H2A1") (pin "1") (pinfunction "1_1") (pintype "passive"))
      (node (ref "S4") (pin "3") (pinfunction "S_3") (pintype "passive"))
    )
    (net (code "39") (name "Net-(S4-S1)") (class "Default")
      (node (ref "R_H2A1") (pin "2") (pinfunction "2_2") (pintype "passive"))
      (node (ref "S4") (pin "6") (pinfunction "S1_6") (pintype "passive"))
    )
    (net (code "40") (name "OP_OUTA") (class "Default")
      (node (ref "H_H1") (pin "2") (pinfunction "2_2") (pintype "passive"))
      (node (ref "H_H4") (pin "2") (pinfunction "2_2") (pintype "passive"))
      (node (ref "OPAMP") (pin "1") (pinfunction "OUTA_1") (pintype "output"))
      (node (ref "OPAMP1") (pin "1") (pinfunction "OUTA_1") (pintype "output"))
      (node (ref "S2") (pin "5") (pinfunction "P1_5") (pintype "passive"))
      (node (ref "S4") (pin "5") (pinfunction "P1_5") (pintype "passive"))
    )
    (net (code "41") (name "OUT_1") (class "Default")
      (node (ref "JP1") (pin "1") (pinfunction "1_1") (pintype "passive"))
      (node (ref "X4") (pin "1") (pinfunction "1_1") (pintype "passive"))
      (node (ref "X5") (pin "1") (pinfunction "1_1") (pintype "passive"))
    )
    (net (code "42") (name "OUT_2") (class "Default")
      (node (ref "JP2") (pin "1") (pinfunction "1_1") (pintype "passive"))
      (node (ref "X4") (pin "2") (pinfunction "2_2") (pintype "passive"))
      (node (ref "X5") (pin "2") (pinfunction "2_2") (pintype "passive"))
    )
    (net (code "43") (name "OUT_3") (class "Default")
      (node (ref "JP3") (pin "1") (pinfunction "1_1") (pintype "passive"))
      (node (ref "X4") (pin "3") (pinfunction "3_3") (pintype "passive"))
      (node (ref "X5") (pin "3") (pinfunction "3_3") (pintype "passive"))
    )
    (net (code "44") (name "OUT_4") (class "Default")
      (node (ref "JP4") (pin "1") (pinfunction "1_1") (pintype "passive"))
      (node (ref "X4") (pin "4") (pinfunction "4_4") (pintype "passive"))
      (node (ref "X5") (pin "4") (pinfunction "4_4") (pintype "passive"))
    )
    (net (code "45") (name "OUT_5") (class "Default")
      (node (ref "JP5") (pin "1") (pinfunction "1_1") (pintype "passive"))
      (node (ref "X4") (pin "5") (pinfunction "5_5") (pintype "passive"))
      (node (ref "X5") (pin "5") (pinfunction "5_5") (pintype "passive"))
    )
    (net (code "46") (name "OUT_6") (class "Default")
      (node (ref "JP6") (pin "1") (pinfunction "1_1") (pintype "passive"))
      (node (ref "X4") (pin "6") (pinfunction "6_6") (pintype "passive"))
      (node (ref "X5") (pin "6") (pinfunction "6_6") (pintype "passive"))
    )
    (net (code "47") (name "OUT_7") (class "Default")
      (node (ref "JP7") (pin "1") (pinfunction "1_1") (pintype "passive"))
      (node (ref "X4") (pin "7") (pinfunction "7_7") (pintype "passive"))
      (node (ref "X5") (pin "7") (pinfunction "7_7") (pintype "passive"))
    )
    (net (code "48") (name "OUT_8") (class "Default")
      (node (ref "JP8") (pin "1") (pinfunction "1_1") (pintype "passive"))
      (node (ref "X4") (pin "8") (pinfunction "8_8") (pintype "passive"))
      (node (ref "X5") (pin "8") (pinfunction "8_8") (pintype "passive"))
    )
    (net (code "49") (name "OUT_9") (class "Default")
      (node (ref "JP9") (pin "1") (pinfunction "1_1") (pintype "passive"))
      (node (ref "X4") (pin "9") (pinfunction "9_9") (pintype "passive"))
      (node (ref "X5") (pin "9") (pinfunction "9_9") (pintype "passive"))
    )
    (net (code "50") (name "OUT_10") (class "Default")
      (node (ref "JP10") (pin "1") (pinfunction "1_1") (pintype "passive"))
      (node (ref "X4") (pin "10") (pinfunction "10_10") (pintype "passive"))
      (node (ref "X5") (pin "10") (pinfunction "10_10") (pintype "passive"))
    )
    (net (code "51") (name "OUT_11") (class "Default")
      (node (ref "JP11") (pin "1") (pinfunction "1_1") (pintype "passive"))
      (node (ref "X4") (pin "11") (pinfunction "11_11") (pintype "passive"))
      (node (ref "X5") (pin "11") (pinfunction "11_11") (pintype "passive"))
    )
    (net (code "52") (name "OUT_12") (class "Default")
      (node (ref "JP12") (pin "1") (pinfunction "1_1") (pintype "passive"))
      (node (ref "X4") (pin "12") (pinfunction "12_12") (pintype "passive"))
      (node (ref "X5") (pin "12") (pinfunction "12_12") (pintype "passive"))
    )
    (net (code "53") (name "OUT_13") (class "Default")
      (node (ref "JP13") (pin "1") (pinfunction "1_1") (pintype "passive"))
      (node (ref "X4") (pin "13") (pinfunction "13_13") (pintype "passive"))
      (node (ref "X5") (pin "13") (pinfunction "13_13") (pintype "passive"))
    )
    (net (code "54") (name "OUT_14") (class "Default")
      (node (ref "JP14") (pin "1") (pinfunction "1_1") (pintype "passive"))
      (node (ref "X4") (pin "14") (pinfunction "14_14") (pintype "passive"))
      (node (ref "X5") (pin "14") (pinfunction "14_14") (pintype "passive"))
    )
    (net (code "55") (name "OUT_15") (class "Default")
      (node (ref "JP15") (pin "1") (pinfunction "1_1") (pintype "passive"))
      (node (ref "X4") (pin "15") (pinfunction "15_15") (pintype "passive"))
      (node (ref "X5") (pin "15") (pinfunction "15_15") (pintype "passive"))
    )
    (net (code "56") (name "OUT_16") (class "Default")
      (node (ref "JP16") (pin "1") (pinfunction "1_1") (pintype "passive"))
      (node (ref "X4") (pin "16") (pinfunction "16_16") (pintype "passive"))
      (node (ref "X5") (pin "16") (pinfunction "16_16") (pintype "passive"))
    )
    (net (code "57") (name "OUT_17") (class "Default")
      (node (ref "JP17") (pin "1") (pinfunction "1_1") (pintype "passive"))
      (node (ref "X4") (pin "17") (pinfunction "17_17") (pintype "passive"))
      (node (ref "X5") (pin "17") (pinfunction "17_17") (pintype "passive"))
    )
    (net (code "58") (name "OUT_18") (class "Default")
      (node (ref "JP18") (pin "1") (pinfunction "1_1") (pintype "passive"))
      (node (ref "X4") (pin "18") (pinfunction "18_18") (pintype "passive"))
      (node (ref "X5") (pin "18") (pinfunction "18_18") (pintype "passive"))
    )
    (net (code "59") (name "OUT_19") (class "Default")
      (node (ref "JP19") (pin "1") (pinfunction "1_1") (pintype "passive"))
      (node (ref "X4") (pin "19") (pinfunction "19_19") (pintype "passive"))
      (node (ref "X5") (pin "19") (pinfunction "19_19") (pintype "passive"))
    )
    (net (code "60") (name "OUT_20") (class "Default")
      (node (ref "JP20") (pin "1") (pinfunction "1_1") (pintype "passive"))
      (node (ref "X4") (pin "20") (pinfunction "20_20") (pintype "passive"))
      (node (ref "X5") (pin "20") (pinfunction "20_20") (pintype "passive"))
    )
    (net (code "61") (name "OUT_21") (class "Default")
      (node (ref "JP21") (pin "1") (pinfunction "1_1") (pintype "passive"))
      (node (ref "X4") (pin "21") (pinfunction "21_21") (pintype "passive"))
      (node (ref "X5") (pin "21") (pinfunction "21_21") (pintype "passive"))
    )
    (net (code "62") (name "OUT_22") (class "Default")
      (node (ref "JP22") (pin "1") (pinfunction "1_1") (pintype "passive"))
      (node (ref "X4") (pin "22") (pinfunction "22_22") (pintype "passive"))
      (node (ref "X5") (pin "22") (pinfunction "22_22") (pintype "passive"))
    )
    (net (code "63") (name "OUT_23") (class "Default")
      (node (ref "JP23") (pin "1") (pinfunction "1_1") (pintype "passive"))
      (node (ref "X4") (pin "23") (pinfunction "23_23") (pintype "passive"))
      (node (ref "X5") (pin "23") (pinfunction "23_23") (pintype "passive"))
    )
    (net (code "64") (name "OUT_24") (class "Default")
      (node (ref "JP24") (pin "1") (pinfunction "1_1") (pintype "passive"))
      (node (ref "X4") (pin "24") (pinfunction "24_24") (pintype "passive"))
      (node (ref "X5") (pin "24") (pinfunction "24_24") (pintype "passive"))
    )
    (net (code "65") (name "OUT_25") (class "Default")
      (node (ref "JP25") (pin "1") (pinfunction "1_1") (pintype "passive"))
      (node (ref "X4") (pin "25") (pinfunction "25_25") (pintype "passive"))
      (node (ref "X5") (pin "25") (pinfunction "25_25") (pintype "passive"))
    )
    (net (code "66") (name "OUT_26") (class "Default")
      (node (ref "JP26") (pin "1") (pinfunction "1_1") (pintype "passive"))
      (node (ref "X4") (pin "26") (pinfunction "26_26") (pintype "passive"))
      (node (ref "X5") (pin "26") (pinfunction "26_26") (pintype "passive"))
    )
    (net (code "67") (name "OUT_27") (class "Default")
      (node (ref "JP27") (pin "1") (pinfunction "1_1") (pintype "passive"))
      (node (ref "X4") (pin "27") (pinfunction "27_27") (pintype "passive"))
      (node (ref "X5") (pin "27") (pinfunction "27_27") (pintype "passive"))
    )
    (net (code "68") (name "OUT_28") (class "Default")
      (node (ref "JP28") (pin "1") (pinfunction "1_1") (pintype "passive"))
      (node (ref "X4") (pin "28") (pinfunction "28_28") (pintype "passive"))
      (node (ref "X5") (pin "28") (pinfunction "28_28") (pintype "passive"))
    )
    (net (code "69") (name "OUT_29") (class "Default")
      (node (ref "JP29") (pin "1") (pinfunction "1_1") (pintype "passive"))
      (node (ref "X4") (pin "29") (pinfunction "29_29") (pintype "passive"))
      (node (ref "X5") (pin "29") (pinfunction "29_29") (pintype "passive"))
    )
    (net (code "70") (name "OUT_30") (class "Default")
      (node (ref "JP30") (pin "1") (pinfunction "1_1") (pintype "passive"))
      (node (ref "X4") (pin "30") (pinfunction "30_30") (pintype "passive"))
      (node (ref "X5") (pin "30") (pinfunction "30_30") (pintype "passive"))
    )
    (net (code "71") (name "OUT_31") (class "Default")
      (node (ref "JP31") (pin "1") (pinfunction "1_1") (pintype "passive"))
      (node (ref "X4") (pin "31") (pinfunction "31_31") (pintype "passive"))
      (node (ref "X5") (pin "31") (pinfunction "31_31") (pintype "passive"))
    )
    (net (code "72") (name "OUT_32") (class "Default")
      (node (ref "JP32") (pin "1") (pinfunction "1_1") (pintype "passive"))
      (node (ref "X4") (pin "32") (pinfunction "32_32") (pintype "passive"))
      (node (ref "X5") (pin "32") (pinfunction "32_32") (pintype "passive"))
    )
    (net (code "73") (name "OUT_33") (class "Default")
      (node (ref "X4") (pin "33") (pinfunction "33_33") (pintype "passive"))
      (node (ref "X5") (pin "33") (pinfunction "33_33") (pintype "passive"))
    )
    (net (code "74") (name "OUT_34") (class "Default")
      (node (ref "X4") (pin "34") (pinfunction "34_34") (pintype "passive"))
      (node (ref "X5") (pin "34") (pinfunction "34_34") (pintype "passive"))
    )
    (net (code "75") (name "OUT_35") (class "Default")
      (node (ref "X4") (pin "35") (pinfunction "35_35") (pintype "passive"))
      (node (ref "X5") (pin "35") (pinfunction "35_35") (pintype "passive"))
    )
    (net (code "76") (name "OUT_36") (class "Default")
      (node (ref "X4") (pin "36") (pinfunction "36_36") (pintype "passive"))
      (node (ref "X5") (pin "36") (pinfunction "36_36") (pintype "passive"))
    )
    (net (code "77") (name "OUT_37") (class "Default")
      (node (ref "X4") (pin "37") (pinfunction "37_37") (pintype "passive"))
      (node (ref "X5") (pin "37") (pinfunction "37_37") (pintype "passive"))
    )
    (net (code "78") (name "SCLK") (class "Default")
      (node (ref "DDS") (pin "7") (pinfunction "SCLK_7") (pintype "input"))
      (node (ref "DDS1") (pin "7") (pinfunction "SCLK_7") (pintype "input"))
      (node (ref "DIGITAL_ISO1") (pin "12") (pinfunction "VOC_12") (pintype "passive"))
      (node (ref "DIGITAL_ISO2") (pin "12") (pinfunction "VOC_12") (pintype "passive"))
    )
    (net (code "79") (name "SCLK_IN") (class "Default")
      (node (ref "DIGITAL_ISO1") (pin "5") (pinfunction "VIC_5") (pintype "passive"))
      (node (ref "DIGITAL_ISO2") (pin "5") (pinfunction "VIC_5") (pintype "passive"))
      (node (ref "X2") (pin "2") (pinfunction "2_2") (pintype "passive"))
    )
    (net (code "80") (name "SDATA") (class "Default")
      (node (ref "DDS") (pin "6") (pinfunction "SDATA_6") (pintype "input"))
      (node (ref "DDS1") (pin "6") (pinfunction "SDATA_6") (pintype "input"))
      (node (ref "DIGITAL_ISO1") (pin "13") (pinfunction "VOB_13") (pintype "passive"))
      (node (ref "DIGITAL_ISO2") (pin "13") (pinfunction "VOB_13") (pintype "passive"))
    )
    (net (code "81") (name "SDATA_IN") (class "Default")
      (node (ref "DIGITAL_ISO1") (pin "4") (pinfunction "VIB_4") (pintype "passive"))
      (node (ref "DIGITAL_ISO2") (pin "4") (pinfunction "VIB_4") (pintype "passive"))
      (node (ref "X2") (pin "3") (pinfunction "3_3") (pintype "passive"))
    )
    (net (code "82") (name "SW_DIN") (class "Default")
      (node (ref "U1") (pin "3") (pinfunction "DIN_3") (pintype "input"))
      (node (ref "X2") (pin "5") (pinfunction "5_5") (pintype "passive"))
    )
    (net (code "83") (name "SW_SCLK") (class "Default")
      (node (ref "U1") (pin "1") (pinfunction "SCLK_1") (pintype "input"))
      (node (ref "X2") (pin "1") (pinfunction "1_1") (pintype "passive"))
    )
    (net (code "84") (name "SW_~{RESET}") (class "Default")
      (node (ref "U1") (pin "23") (pinfunction "~{RESET}_23") (pintype "input"))
      (node (ref "X2") (pin "8") (pinfunction "8_8") (pintype "passive"))
    )
    (net (code "85") (name "SW_~{SYNC}") (class "Default")
      (node (ref "U1") (pin "24") (pinfunction "~{SYNC}_24") (pintype "input"))
      (node (ref "X2") (pin "7") (pinfunction "7_7") (pintype "passive"))
    )
    (net (code "86") (name "VDD") (class "Default")
      (node (ref "C_IN") (pin "1") (pinfunction "1_1") (pintype "passive"))
      (node (ref "C_IN1") (pin "1") (pinfunction "1_1") (pintype "passive"))
      (node (ref "JP33") (pin "2") (pinfunction "2_2") (pintype "passive"))
      (node (ref "JP34") (pin "1") (pinfunction "1_1") (pintype "passive"))
      (node (ref "S1") (pin "3") (pinfunction "S_3") (pintype "passive"))
      (node (ref "S3") (pin "3") (pinfunction "S_3") (pintype "passive"))
      (node (ref "U$1") (pin "VIN@1") (pinfunction "VIN_VIN@1") (pintype "bidirectional"))
      (node (ref "U$1") (pin "VIN@2") (pinfunction "VIN_VIN@2") (pintype "bidirectional"))
      (node (ref "U$1") (pin "VIN@3") (pinfunction "VIN_VIN@3") (pintype "bidirectional"))
      (node (ref "U$1") (pin "VIN@4") (pinfunction "VIN_VIN@4") (pintype "bidirectional"))
      (node (ref "U$2") (pin "VIN@1") (pinfunction "VIN_VIN@1") (pintype "bidirectional"))
      (node (ref "U$2") (pin "VIN@2") (pinfunction "VIN_VIN@2") (pintype "bidirectional"))
      (node (ref "U$2") (pin "VIN@3") (pinfunction "VIN_VIN@3") (pintype "bidirectional"))
      (node (ref "U$2") (pin "VIN@4") (pinfunction "VIN_VIN@4") (pintype "bidirectional"))
    )
    (net (code "87") (name "VDD_CS_ANA") (class "Default")
      (node (ref "C_BYP") (pin "2") (pinfunction "2_2") (pintype "passive"))
      (node (ref "C_BYP1") (pin "2") (pinfunction "2_2") (pintype "passive"))
      (node (ref "C_DDS_BYP3") (pin "1") (pinfunction "1_1") (pintype "passive"))
      (node (ref "C_DDS_BYP4") (pin "1") (pinfunction "1_1") (pintype "passive"))
      (node (ref "C_DDS_BYP7") (pin "1") (pinfunction "1_1") (pintype "passive"))
      (node (ref "C_DDS_BYP8") (pin "1") (pinfunction "1_1") (pintype "passive"))
      (node (ref "C_OUT2") (pin "2") (pinfunction "2_2") (pintype "passive"))
      (node (ref "C_OUT4") (pin "2") (pinfunction "2_2") (pintype "passive"))
      (node (ref "OPAMP") (pin "8") (pinfunction "V+_8") (pintype "power_in"))
      (node (ref "OPAMP1") (pin "8") (pinfunction "V+_8") (pintype "power_in"))
      (node (ref "U$1") (pin "VOUT2@1") (pinfunction "VOUT2_VOUT2@1") (pintype "bidirectional"))
      (node (ref "U$1") (pin "VOUT2@2") (pinfunction "VOUT2_VOUT2@2") (pintype "bidirectional"))
      (node (ref "U$1") (pin "VOUT2@3") (pinfunction "VOUT2_VOUT2@3") (pintype "bidirectional"))
      (node (ref "U$1") (pin "VOUT2@4") (pinfunction "VOUT2_VOUT2@4") (pintype "bidirectional"))
      (node (ref "U$2") (pin "VOUT2@1") (pinfunction "VOUT2_VOUT2@1") (pintype "bidirectional"))
      (node (ref "U$2") (pin "VOUT2@2") (pinfunction "VOUT2_VOUT2@2") (pintype "bidirectional"))
      (node (ref "U$2") (pin "VOUT2@3") (pinfunction "VOUT2_VOUT2@3") (pintype "bidirectional"))
      (node (ref "U$2") (pin "VOUT2@4") (pinfunction "VOUT2_VOUT2@4") (pintype "bidirectional"))
    )
    (net (code "88") (name "VDD_CS_DIG") (class "Default")
      (node (ref "CLOCK") (pin "6") (pinfunction "V+_6") (pintype "power_in"))
      (node (ref "CLOCK1") (pin "6") (pinfunction "V+_6") (pintype "power_in"))
      (node (ref "C_CLK_BYP") (pin "1") (pinfunction "1_1") (pintype "passive"))
      (node (ref "C_CLK_BYP1") (pin "1") (pinfunction "1_1") (pintype "passive"))
      (node (ref "C_DDS2") (pin "1") (pinfunction "1_1") (pintype "passive"))
      (node (ref "C_DDS3") (pin "1") (pinfunction "1_1") (pintype "passive"))
      (node (ref "C_DDS_BYP1") (pin "1") (pinfunction "1_1") (pintype "passive"))
      (node (ref "C_DDS_BYP2") (pin "1") (pinfunction "1_1") (pintype "passive"))
      (node (ref "C_DDS_BYP5") (pin "1") (pinfunction "1_1") (pintype "passive"))
      (node (ref "C_DDS_BYP6") (pin "1") (pinfunction "1_1") (pintype "passive"))
      (node (ref "C_ISO2A") (pin "1") (pinfunction "1_1") (pintype "passive"))
      (node (ref "C_ISO2A1") (pin "1") (pinfunction "1_1") (pintype "passive"))
      (node (ref "C_ISO2B") (pin "1") (pinfunction "1_1") (pintype "passive"))
      (node (ref "C_ISO2B1") (pin "1") (pinfunction "1_1") (pintype "passive"))
      (node (ref "C_OUT1") (pin "2") (pinfunction "2_2") (pintype "passive"))
      (node (ref "C_OUT3") (pin "2") (pinfunction "2_2") (pintype "passive"))
      (node (ref "DDS") (pin "2") (pinfunction "VDD_2") (pintype "power_in"))
      (node (ref "DDS1") (pin "2") (pinfunction "VDD_2") (pintype "power_in"))
      (node (ref "DIGITAL_ISO1") (pin "16") (pinfunction "VDD2_16") (pintype "power_in"))
      (node (ref "DIGITAL_ISO2") (pin "16") (pinfunction "VDD2_16") (pintype "power_in"))
      (node (ref "R_LED") (pin "2") (pinfunction "2_2") (pintype "passive"))
      (node (ref "R_LED1") (pin "2") (pinfunction "2_2") (pintype "passive"))
      (node (ref "U$1") (pin "VOUT1@1") (pinfunction "VOUT1_VOUT1@1") (pintype "bidirectional"))
      (node (ref "U$1") (pin "VOUT1@2") (pinfunction "VOUT1_VOUT1@2") (pintype "bidirectional"))
      (node (ref "U$1") (pin "VOUT1@3") (pinfunction "VOUT1_VOUT1@3") (pintype "bidirectional"))
      (node (ref "U$1") (pin "VOUT1@4") (pinfunction "VOUT1_VOUT1@4") (pintype "bidirectional"))
      (node (ref "U$1") (pin "VOUT1@5") (pinfunction "VOUT1_VOUT1@5") (pintype "bidirectional"))
      (node (ref "U$1") (pin "VOUT1@6") (pinfunction "VOUT1_VOUT1@6") (pintype "bidirectional"))
      (node (ref "U$2") (pin "VOUT1@1") (pinfunction "VOUT1_VOUT1@1") (pintype "bidirectional"))
      (node (ref "U$2") (pin "VOUT1@2") (pinfunction "VOUT1_VOUT1@2") (pintype "bidirectional"))
      (node (ref "U$2") (pin "VOUT1@3") (pinfunction "VOUT1_VOUT1@3") (pintype "bidirectional"))
      (node (ref "U$2") (pin "VOUT1@4") (pinfunction "VOUT1_VOUT1@4") (pintype "bidirectional"))
      (node (ref "U$2") (pin "VOUT1@5") (pinfunction "VOUT1_VOUT1@5") (pintype "bidirectional"))
      (node (ref "U$2") (pin "VOUT1@6") (pinfunction "VOUT1_VOUT1@6") (pintype "bidirectional"))
    )
    (net (code "89") (name "unconnected-(DIGITAL_ISO1-CTRL2-Pad10)") (class "Default")
      (node (ref "DIGITAL_ISO1") (pin "10") (pinfunction "CTRL2_10") (pintype "passive"))
    )
    (net (code "90") (name "unconnected-(DIGITAL_ISO1-VID-Pad6)") (class "Default")
      (node (ref "DIGITAL_ISO1") (pin "6") (pinfunction "VID_6") (pintype "passive"))
    )
    (net (code "91") (name "unconnected-(DIGITAL_ISO1-VOD-Pad11)") (class "Default")
      (node (ref "DIGITAL_ISO1") (pin "11") (pinfunction "VOD_11") (pintype "passive"))
    )
    (net (code "92") (name "unconnected-(DIGITAL_ISO2-CTRL2-Pad10)") (class "Default")
      (node (ref "DIGITAL_ISO2") (pin "10") (pinfunction "CTRL2_10") (pintype "passive"))
    )
    (net (code "93") (name "unconnected-(DIGITAL_ISO2-VID-Pad6)") (class "Default")
      (node (ref "DIGITAL_ISO2") (pin "6") (pinfunction "VID_6") (pintype "passive"))
    )
    (net (code "94") (name "unconnected-(DIGITAL_ISO2-VOD-Pad11)") (class "Default")
      (node (ref "DIGITAL_ISO2") (pin "11") (pinfunction "VOD_11") (pintype "passive"))
    )
    (net (code "95") (name "unconnected-(OPAMP-NEGB-Pad6)") (class "Default")
      (node (ref "OPAMP") (pin "6") (pinfunction "NEGB_6") (pintype "input"))
    )
    (net (code "96") (name "unconnected-(OPAMP-OUTB-Pad7)") (class "Default")
      (node (ref "OPAMP") (pin "7") (pinfunction "OUTB_7") (pintype "output"))
    )
    (net (code "97") (name "unconnected-(OPAMP-POSB-Pad5)") (class "Default")
      (node (ref "OPAMP") (pin "5") (pinfunction "POSB_5") (pintype "input"))
    )
    (net (code "98") (name "unconnected-(OPAMP1-NEGB-Pad6)") (class "Default")
      (node (ref "OPAMP1") (pin "6") (pinfunction "NEGB_6") (pintype "input"))
    )
    (net (code "99") (name "unconnected-(OPAMP1-OUTB-Pad7)") (class "Default")
      (node (ref "OPAMP1") (pin "7") (pinfunction "OUTB_7") (pintype "output"))
    )
    (net (code "100") (name "unconnected-(OPAMP1-POSB-Pad5)") (class "Default")
      (node (ref "OPAMP1") (pin "5") (pinfunction "POSB_5") (pintype "input"))
    )
    (net (code "101") (name "unconnected-(U$1-PadSS)") (class "Default")
      (node (ref "U$1") (pin "SS") (pinfunction "SS_SS") (pintype "bidirectional"))
    )
    (net (code "102") (name "unconnected-(U$2-PadSS)") (class "Default")
      (node (ref "U$2") (pin "SS") (pinfunction "SS_SS") (pintype "bidirectional"))
    )
    (net (code "103") (name "unconnected-(U1-D2-Pad8)") (class "Default")
      (node (ref "U1") (pin "8") (pinfunction "D2_8") (pintype "bidirectional"))
    )
    (net (code "104") (name "unconnected-(U1-D3-Pad10)") (class "Default")
      (node (ref "U1") (pin "10") (pinfunction "D3_10") (pintype "bidirectional"))
    )
    (net (code "105") (name "unconnected-(U1-D4-Pad12)") (class "Default")
      (node (ref "U1") (pin "12") (pinfunction "D4_12") (pintype "bidirectional"))
    )
    (net (code "106") (name "unconnected-(U1-D5-Pad13)") (class "Default")
      (node (ref "U1") (pin "13") (pinfunction "D5_13") (pintype "bidirectional"))
    )
    (net (code "107") (name "unconnected-(U1-D6-Pad15)") (class "Default")
      (node (ref "U1") (pin "15") (pinfunction "D6_15") (pintype "bidirectional"))
    )
    (net (code "108") (name "unconnected-(U1-D7-Pad17)") (class "Default")
      (node (ref "U1") (pin "17") (pinfunction "D7_17") (pintype "bidirectional"))
    )
    (net (code "109") (name "unconnected-(U1-D8-Pad19)") (class "Default")
      (node (ref "U1") (pin "19") (pinfunction "D8_19") (pintype "bidirectional"))
    )
    (net (code "110") (name "unconnected-(U1-DOUT-Pad22)") (class "Default")
      (node (ref "U1") (pin "22") (pinfunction "DOUT_22") (pintype "output"))
    )
    (net (code "111") (name "unconnected-(X2-PadG1)") (class "Default")
      (node (ref "X2") (pin "G1") (pinfunction "G1_G1") (pintype "passive"))
    )
    (net (code "112") (name "unconnected-(X2-PadG2)") (class "Default")
      (node (ref "X2") (pin "G2") (pinfunction "G2_G2") (pintype "passive"))
    )
    (net (code "113") (name "unconnected-(X4-PadG1)") (class "Default")
      (node (ref "X4") (pin "G1") (pinfunction "G1_G1") (pintype "passive"))
    )
    (net (code "114") (name "unconnected-(X4-PadG2)") (class "Default")
      (node (ref "X4") (pin "G2") (pinfunction "G2_G2") (pintype "passive"))
    )
    (net (code "115") (name "unconnected-(X5-PadG1)") (class "Default")
      (node (ref "X5") (pin "G1") (pinfunction "G1_G1") (pintype "passive"))
    )
    (net (code "116") (name "unconnected-(X5-PadG2)") (class "Default")
      (node (ref "X5") (pin "G2") (pinfunction "G2_G2") (pintype "passive"))
    )
  )
)
